# design.net
KiCad netlist of a schematic drawn in Altium Designer
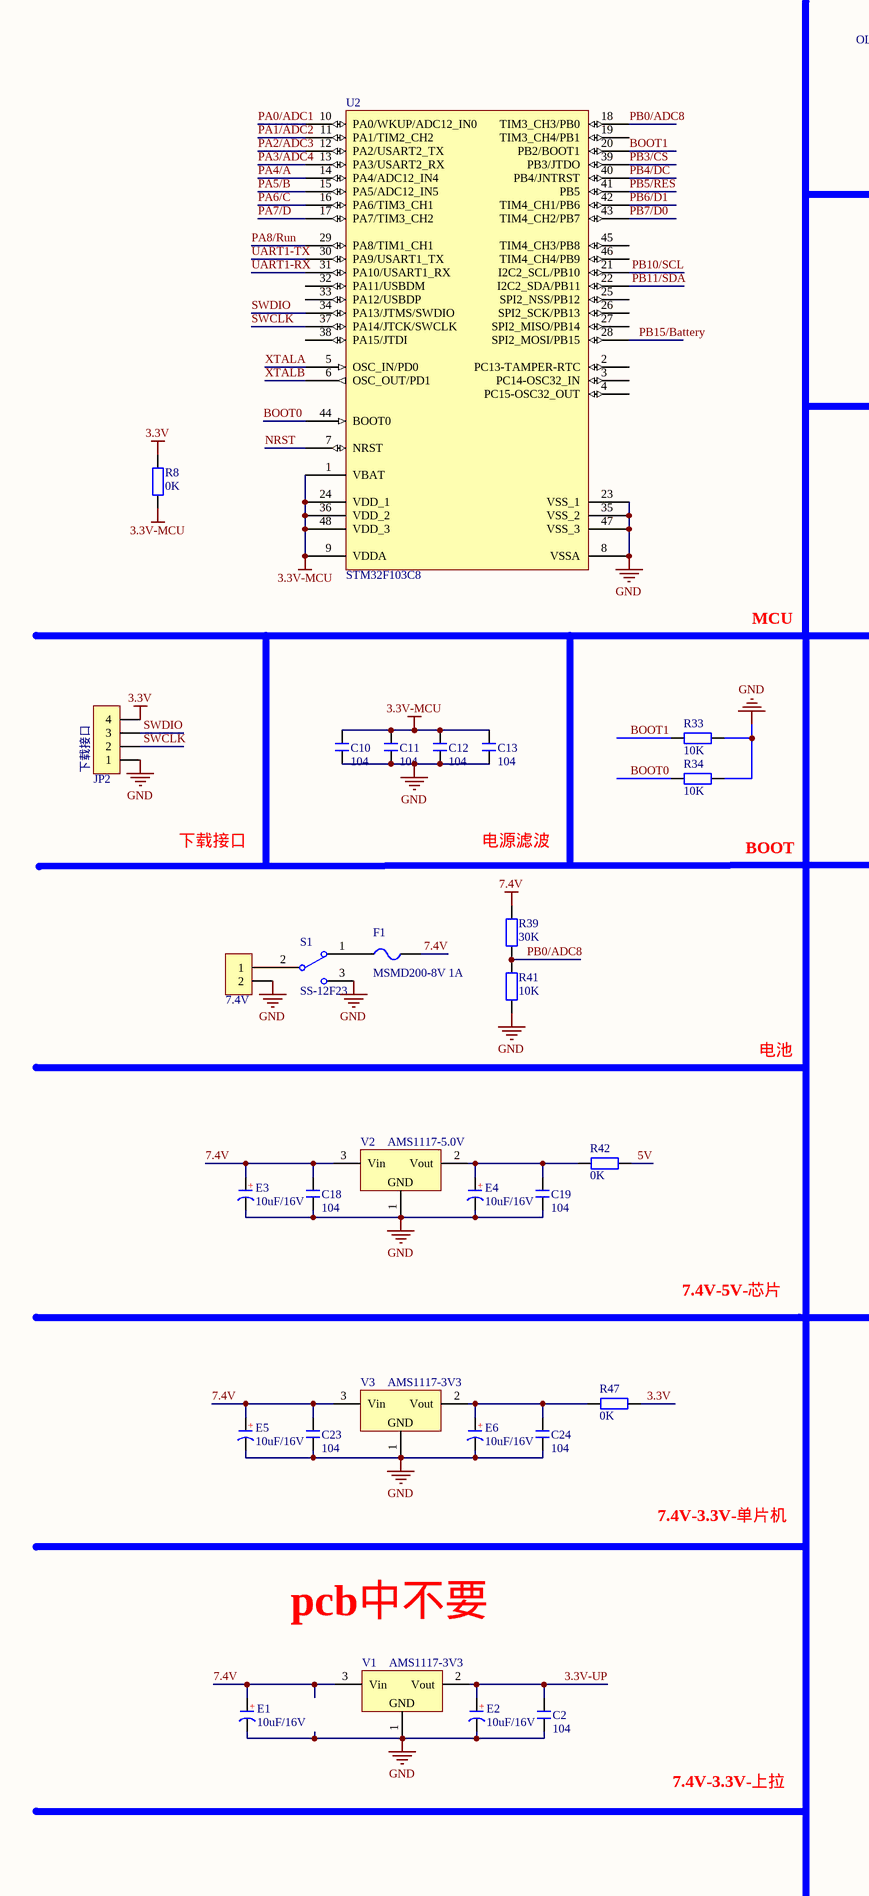
[diagram p0: 足底压力.SchDoc, left]
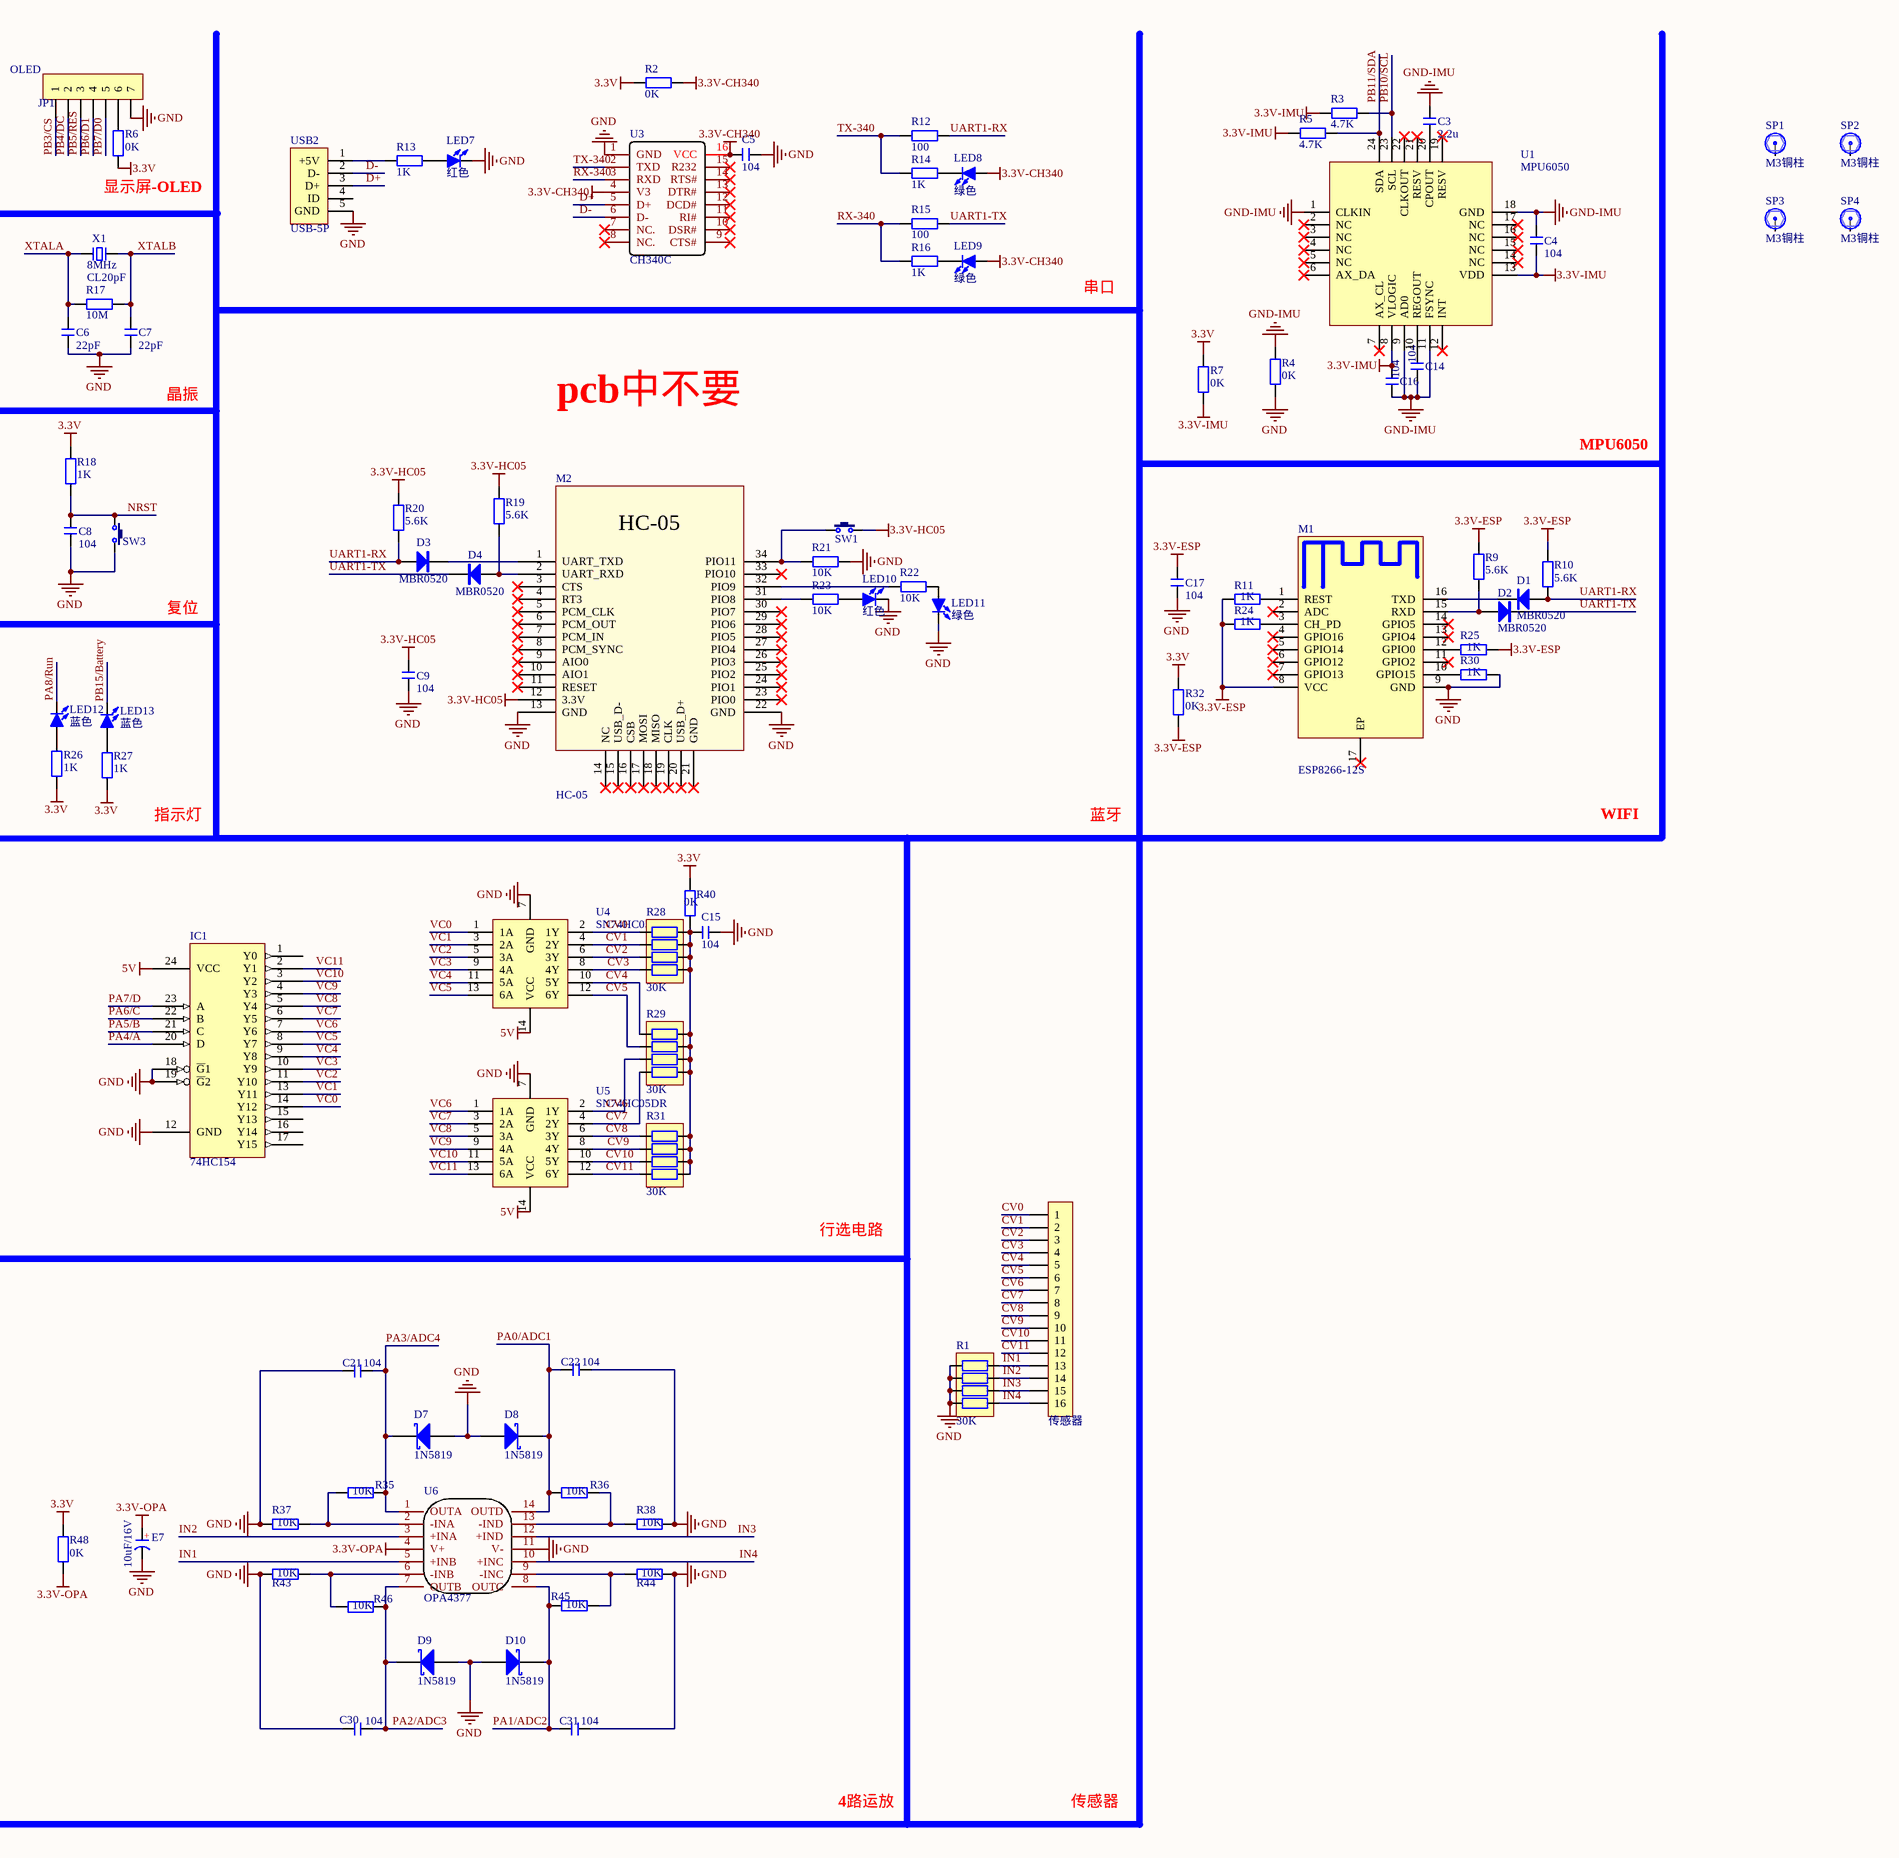
[diagram p1: 足底压力.SchDoc, right]

(export (version "E")
  (design (tool "Eeschema 10.0.6"))
  (components
    (comp (ref "7.4V")
      (value "HDR-1X2")
      (footprint "XH2.54-WI-2P")
      (description "2P接插件")
      (fields (field (name "版权归属") "封装库来自淘宝 ID：黄晶宝石"))
      (libsource (lib "5.3 - 接插件-脚距2.54 (100mil) ") (part "Header 2"))
    )
    (comp (ref "C2")
      (value "104")
      (footprint "C 0603_L")
      (description "贴片电容")
      (libsource (lib "0.1 - 电阻-电容-电感") (part "C"))
    )
    (comp (ref "C3")
      (value "2.2u")
      (footprint "C 0603_L")
      (description "贴片电容")
      (libsource (lib "0.1 - 电阻-电容-电感") (part "C"))
    )
    (comp (ref "C4")
      (value "104")
      (footprint "C 0603_L")
      (description "贴片电容")
      (libsource (lib "0.1 - 电阻-电容-电感") (part "C"))
    )
    (comp (ref "C5")
      (value "104")
      (footprint "C 0603_L")
      (description "贴片电容")
      (libsource (lib "0.1 - 电阻-电容-电感") (part "C"))
    )
    (comp (ref "C6")
      (value "22pF")
      (footprint "C 0603_L")
      (description "贴片电容")
      (libsource (lib "0.1 - 电阻-电容-电感") (part "C"))
    )
    (comp (ref "C7")
      (value "22pF")
      (footprint "C 0603_L")
      (description "贴片电容")
      (libsource (lib "0.1 - 电阻-电容-电感") (part "C"))
    )
    (comp (ref "C8")
      (value "104")
      (footprint "C 0603_L")
      (description "贴片电容")
      (libsource (lib "0.1 - 电阻-电容-电感") (part "C"))
    )
    (comp (ref "C9")
      (value "104")
      (footprint "C 0805_L")
      (description "贴片电容")
      (libsource (lib "0.1 - 电阻-电容-电感") (part "C"))
    )
    (comp (ref "C10")
      (value "104")
      (footprint "C 0603_L")
      (description "贴片电容")
      (libsource (lib "0.1 - 电阻-电容-电感") (part "C"))
    )
    (comp (ref "C11")
      (value "104")
      (footprint "C 0603_L")
      (description "贴片电容")
      (libsource (lib "0.1 - 电阻-电容-电感") (part "C"))
    )
    (comp (ref "C12")
      (value "104")
      (footprint "C 0603_L")
      (description "贴片电容")
      (libsource (lib "0.1 - 电阻-电容-电感") (part "C"))
    )
    (comp (ref "C13")
      (value "104")
      (footprint "C 0603_L")
      (description "贴片电容")
      (libsource (lib "0.1 - 电阻-电容-电感") (part "C"))
    )
    (comp (ref "C14")
      (value "104")
      (footprint "C 0603_L")
      (description "贴片电容")
      (libsource (lib "0.1 - 电阻-电容-电感") (part "C"))
    )
    (comp (ref "C15")
      (value "104")
      (footprint "C 0603_L")
      (description "贴片电容")
      (libsource (lib "0.1 - 电阻-电容-电感") (part "C"))
    )
    (comp (ref "C16")
      (value "104")
      (footprint "C 0603_L")
      (description "贴片电容")
      (libsource (lib "0.1 - 电阻-电容-电感") (part "C"))
    )
    (comp (ref "C17")
      (value "104")
      (footprint "C 0603_L")
      (description "贴片电容")
      (libsource (lib "0.1 - 电阻-电容-电感") (part "C"))
    )
    (comp (ref "C18")
      (value "104")
      (footprint "C 0603_L")
      (description "贴片电容")
      (libsource (lib "0.1 - 电阻-电容-电感") (part "C"))
    )
    (comp (ref "C19")
      (value "104")
      (footprint "C 0603_L")
      (description "贴片电容")
      (libsource (lib "0.1 - 电阻-电容-电感") (part "C"))
    )
    (comp (ref "C21")
      (value "104")
      (footprint "C 0603_L")
      (description "贴片电容")
      (libsource (lib "0.1 - 电阻-电容-电感") (part "C"))
    )
    (comp (ref "C22")
      (value "104")
      (footprint "C 0603_L")
      (description "贴片电容")
      (libsource (lib "0.1 - 电阻-电容-电感") (part "C"))
    )
    (comp (ref "C23")
      (value "104")
      (footprint "C 0603_L")
      (description "贴片电容")
      (libsource (lib "0.1 - 电阻-电容-电感") (part "C"))
    )
    (comp (ref "C24")
      (value "104")
      (footprint "C 0603_L")
      (description "贴片电容")
      (libsource (lib "0.1 - 电阻-电容-电感") (part "C"))
    )
    (comp (ref "C30")
      (value "104")
      (footprint "C 0603_L")
      (description "贴片电容")
      (libsource (lib "0.1 - 电阻-电容-电感") (part "C"))
    )
    (comp (ref "C31")
      (value "104")
      (footprint "C 0603_L")
      (description "贴片电容")
      (libsource (lib "0.1 - 电阻-电容-电感") (part "C"))
    )
    (comp (ref "D1")
      (value "MBR0520")
      (footprint "SOD-123")
      (description "整流二极管")
      (libsource (lib "0.2 -  二极管-整流桥") (part "1N4007"))
    )
    (comp (ref "D2")
      (value "MBR0520")
      (footprint "SOD-123")
      (description "整流二极管")
      (libsource (lib "0.2 -  二极管-整流桥") (part "1N4007"))
    )
    (comp (ref "D3")
      (value "MBR0520")
      (footprint "SOD-123")
      (description "整流二极管")
      (libsource (lib "0.2 -  二极管-整流桥") (part "1N4007"))
    )
    (comp (ref "D4")
      (value "MBR0520")
      (footprint "SOD-123")
      (description "整流二极管")
      (libsource (lib "0.2 -  二极管-整流桥") (part "1N4007"))
    )
    (comp (ref "D7")
      (value "1N5819")
      (footprint "SOD-123")
      (description "肖特基二极管")
      (libsource (lib "0.2 -  二极管-整流桥") (part "1N5819"))
    )
    (comp (ref "D8")
      (value "1N5819")
      (footprint "SOD-123")
      (description "肖特基二极管")
      (libsource (lib "0.2 -  二极管-整流桥") (part "1N5819"))
    )
    (comp (ref "D9")
      (value "1N5819")
      (footprint "SOD-123")
      (description "肖特基二极管")
      (libsource (lib "0.2 -  二极管-整流桥") (part "1N5819"))
    )
    (comp (ref "D10")
      (value "1N5819")
      (footprint "SOD-123")
      (description "肖特基二极管")
      (libsource (lib "0.2 -  二极管-整流桥") (part "1N5819"))
    )
    (comp (ref "E1")
      (value "10uF/16V")
      (footprint "CD A(3216)")
      (description "贴片钽电容")
      (libsource (lib "0.1 - 电阻-电容-电感") (part "CT"))
    )
    (comp (ref "E2")
      (value "10uF/16V")
      (footprint "CD A(3216)")
      (description "贴片钽电容")
      (libsource (lib "0.1 - 电阻-电容-电感") (part "CT"))
    )
    (comp (ref "E3")
      (value "10uF/16V")
      (footprint "CD A(3216)")
      (description "贴片钽电容")
      (libsource (lib "0.1 - 电阻-电容-电感") (part "CT"))
    )
    (comp (ref "E4")
      (value "10uF/16V")
      (footprint "CD A(3216)")
      (description "贴片钽电容")
      (libsource (lib "0.1 - 电阻-电容-电感") (part "CT"))
    )
    (comp (ref "E5")
      (value "10uF/16V")
      (footprint "CD A(3216)")
      (description "贴片钽电容")
      (libsource (lib "0.1 - 电阻-电容-电感") (part "CT"))
    )
    (comp (ref "E6")
      (value "10uF/16V")
      (footprint "CD A(3216)")
      (description "贴片钽电容")
      (libsource (lib "0.1 - 电阻-电容-电感") (part "CT"))
    )
    (comp (ref "E7")
      (value "10uF/16V")
      (footprint "CD A(3216)")
      (description "贴片钽电容")
      (libsource (lib "0.1 - 电阻-电容-电感") (part "CT"))
    )
    (comp (ref "F1")
      (value "MSMD200-8V 1A")
      (footprint "FU 1206")
      (description "贴片保险丝")
      (fields (field (name "版权归属") "封装库来自淘宝卖家 ID：黄晶宝石"))
      (libsource (lib "2.0 - 保险丝-晶振-光耦") (part "FU"))
    )
    (comp (ref "IC1")
      (value "74HC154")
      (footprint "SOP24_N")
      (description "4线转16线译码器")
      (fields (field (name "版权归属") "源创客"))
      (libsource (lib "74系列芯片") (part "74HC154"))
    )
    (comp (ref "JP1")
      (value "HDR-1X7")
      (footprint "HDR2.54-M-LI-7P")
      (description "7P接插件")
      (fields (field (name "版权归属") "封装库来自淘宝 ID：黄晶宝石"))
      (libsource (lib "5.3 - 接插件-脚距2.54 (100mil) ") (part "Header 7"))
    )
    (comp (ref "JP2")
      (value "HDR-1X4")
      (footprint "HDR2.54-LI-4P")
      (description "4P接插件")
      (fields (field (name "版权归属") "封装库来自淘宝 ID：黄晶宝石"))
      (libsource (lib "5.3 - 接插件-脚距2.54 (100mil) ") (part "Header 4"))
    )
    (comp (ref "LED7")
      (value "红色")
      (footprint "LED 0603R")
      (description "贴片LED")
      (fields (field (name "版权归属") "封装库来自淘宝 ID：黄晶宝石"))
      (libsource (lib "0.3 - LED发光二极管") (part "LED-SMD"))
    )
    (comp (ref "LED8")
      (value "绿色")
      (footprint "LED 0603G")
      (description "贴片LED")
      (fields (field (name "版权归属") "封装库来自淘宝 ID：黄晶宝石"))
      (libsource (lib "0.3 - LED发光二极管") (part "LED-SMD"))
    )
    (comp (ref "LED9")
      (value "绿色")
      (footprint "LED 0603G")
      (description "贴片LED")
      (fields (field (name "版权归属") "封装库来自淘宝 ID：黄晶宝石"))
      (libsource (lib "0.3 - LED发光二极管") (part "LED-SMD"))
    )
    (comp (ref "LED10")
      (value "红色")
      (footprint "LED 0805R")
      (description "贴片LED")
      (fields (field (name "版权归属") "封装库来自淘宝 ID：黄晶宝石"))
      (libsource (lib "0.3 - LED发光二极管") (part "LED-SMD"))
    )
    (comp (ref "LED11")
      (value "绿色")
      (footprint "LED 0805G")
      (description "贴片LED")
      (fields (field (name "版权归属") "封装库来自淘宝 ID：黄晶宝石"))
      (libsource (lib "0.3 - LED发光二极管") (part "LED-SMD"))
    )
    (comp (ref "LED12")
      (value "蓝色")
      (footprint "LED 0603B")
      (description "贴片LED")
      (fields (field (name "版权归属") "封装库来自淘宝 ID：黄晶宝石"))
      (libsource (lib "0.3 - LED发光二极管") (part "LED-SMD"))
    )
    (comp (ref "LED13")
      (value "蓝色")
      (footprint "LED 0603B")
      (description "贴片LED")
      (fields (field (name "版权归属") "封装库来自淘宝 ID：黄晶宝石"))
      (libsource (lib "0.3 - LED发光二极管") (part "LED-SMD"))
    )
    (comp (ref "M1")
      (value "ESP8266-12S")
      (footprint "ESP8266-12S")
      (description "立创商城")
      (libsource (lib "模块") (part "ESP8266-12S"))
    )
    (comp (ref "M2")
      (value "HC-05")
      (footprint "HC-05")
      (description "串口蓝牙模块")
      (fields (field (name "版权归属") "源创客"))
      (libsource (lib "模块") (part "HC-05"))
    )
    (comp (ref "R1")
      (value "30K")
      (footprint "RCA-8P4R-0603")
      (description "贴片排阻")
      (fields (field (name "版权归属") "封装库来自淘宝 ID：黄晶宝石"))
      (libsource (lib "") (part "R-8P4R_1"))
    )
    (comp (ref "R2")
      (value "0K")
      (footprint "R 0402_L")
      (description "贴片电阻")
      (fields (field (name "版权归属") "来自淘宝 ID：黄晶宝石"))
      (libsource (lib "0.1 - 电阻-电容-电感") (part "R"))
    )
    (comp (ref "R3")
      (value "4.7K")
      (footprint "R 0603_L")
      (description "贴片电阻")
      (fields (field (name "版权归属") "来自淘宝 ID：黄晶宝石"))
      (libsource (lib "0.1 - 电阻-电容-电感") (part "R"))
    )
    (comp (ref "R4")
      (value "0K")
      (footprint "R 0402_L")
      (description "贴片电阻")
      (fields (field (name "版权归属") "来自淘宝 ID：黄晶宝石"))
      (libsource (lib "0.1 - 电阻-电容-电感") (part "R"))
    )
    (comp (ref "R5")
      (value "4.7K")
      (footprint "R 0603_L")
      (description "贴片电阻")
      (fields (field (name "版权归属") "来自淘宝 ID：黄晶宝石"))
      (libsource (lib "0.1 - 电阻-电容-电感") (part "R"))
    )
    (comp (ref "R6")
      (value "0K")
      (footprint "R 0402_L")
      (description "贴片电阻")
      (fields (field (name "版权归属") "来自淘宝 ID：黄晶宝石"))
      (libsource (lib "0.1 - 电阻-电容-电感") (part "R"))
    )
    (comp (ref "R7")
      (value "0K")
      (footprint "R 0402_L")
      (description "贴片电阻")
      (fields (field (name "版权归属") "来自淘宝 ID：黄晶宝石"))
      (libsource (lib "0.1 - 电阻-电容-电感") (part "R"))
    )
    (comp (ref "R8")
      (value "0K")
      (footprint "R 0402_L")
      (description "贴片电阻")
      (fields (field (name "版权归属") "来自淘宝 ID：黄晶宝石"))
      (libsource (lib "0.1 - 电阻-电容-电感") (part "R"))
    )
    (comp (ref "R9")
      (value "5.6K")
      (footprint "R 0603_L")
      (description "贴片电阻")
      (fields (field (name "版权归属") "来自淘宝 ID：黄晶宝石"))
      (libsource (lib "0.1 - 电阻-电容-电感") (part "R"))
    )
    (comp (ref "R10")
      (value "5.6K")
      (footprint "R 0603_L")
      (description "贴片电阻")
      (fields (field (name "版权归属") "来自淘宝 ID：黄晶宝石"))
      (libsource (lib "0.1 - 电阻-电容-电感") (part "R"))
    )
    (comp (ref "R11")
      (value "1K")
      (footprint "R 0603_L")
      (description "贴片电阻")
      (fields (field (name "版权归属") "来自淘宝 ID：黄晶宝石"))
      (libsource (lib "0.1 - 电阻-电容-电感") (part "R"))
    )
    (comp (ref "R12")
      (value "100")
      (footprint "R 0603_L")
      (description "贴片电阻")
      (fields (field (name "版权归属") "来自淘宝 ID：黄晶宝石"))
      (libsource (lib "0.1 - 电阻-电容-电感") (part "R"))
    )
    (comp (ref "R13")
      (value "1K")
      (footprint "R 0603_L")
      (description "贴片电阻")
      (fields (field (name "版权归属") "来自淘宝 ID：黄晶宝石"))
      (libsource (lib "0.1 - 电阻-电容-电感") (part "R"))
    )
    (comp (ref "R14")
      (value "1K")
      (footprint "R 0603_L")
      (description "贴片电阻")
      (fields (field (name "版权归属") "来自淘宝 ID：黄晶宝石"))
      (libsource (lib "0.1 - 电阻-电容-电感") (part "R"))
    )
    (comp (ref "R15")
      (value "100")
      (footprint "R 0603_L")
      (description "贴片电阻")
      (fields (field (name "版权归属") "来自淘宝 ID：黄晶宝石"))
      (libsource (lib "0.1 - 电阻-电容-电感") (part "R"))
    )
    (comp (ref "R16")
      (value "1K")
      (footprint "R 0603_L")
      (description "贴片电阻")
      (fields (field (name "版权归属") "来自淘宝 ID：黄晶宝石"))
      (libsource (lib "0.1 - 电阻-电容-电感") (part "R"))
    )
    (comp (ref "R17")
      (value "10M")
      (footprint "R 0603_L")
      (description "贴片电阻")
      (fields (field (name "版权归属") "来自淘宝 ID：黄晶宝石"))
      (libsource (lib "0.1 - 电阻-电容-电感") (part "R"))
    )
    (comp (ref "R18")
      (value "1K")
      (footprint "R 0603_L")
      (description "贴片电阻")
      (fields (field (name "版权归属") "来自淘宝 ID：黄晶宝石"))
      (libsource (lib "0.1 - 电阻-电容-电感") (part "R"))
    )
    (comp (ref "R19")
      (value "5.6K")
      (footprint "R 0805_L")
      (description "贴片电阻")
      (fields (field (name "版权归属") "来自淘宝 ID：黄晶宝石"))
      (libsource (lib "0.1 - 电阻-电容-电感") (part "R"))
    )
    (comp (ref "R20")
      (value "5.6K")
      (footprint "R 0805_L")
      (description "贴片电阻")
      (fields (field (name "版权归属") "来自淘宝 ID：黄晶宝石"))
      (libsource (lib "0.1 - 电阻-电容-电感") (part "R"))
    )
    (comp (ref "R21")
      (value "10K")
      (footprint "R 0805_L")
      (description "贴片电阻")
      (fields (field (name "版权归属") "来自淘宝 ID：黄晶宝石"))
      (libsource (lib "0.1 - 电阻-电容-电感") (part "R"))
    )
    (comp (ref "R22")
      (value "10K")
      (footprint "R 0805_L")
      (description "贴片电阻")
      (fields (field (name "版权归属") "来自淘宝 ID：黄晶宝石"))
      (libsource (lib "0.1 - 电阻-电容-电感") (part "R"))
    )
    (comp (ref "R23")
      (value "10K")
      (footprint "R 0805_L")
      (description "贴片电阻")
      (fields (field (name "版权归属") "来自淘宝 ID：黄晶宝石"))
      (libsource (lib "0.1 - 电阻-电容-电感") (part "R"))
    )
    (comp (ref "R24")
      (value "1K")
      (footprint "R 0603_L")
      (description "贴片电阻")
      (fields (field (name "版权归属") "来自淘宝 ID：黄晶宝石"))
      (libsource (lib "0.1 - 电阻-电容-电感") (part "R"))
    )
    (comp (ref "R25")
      (value "1K")
      (footprint "R 0603_L")
      (description "贴片电阻")
      (fields (field (name "版权归属") "来自淘宝 ID：黄晶宝石"))
      (libsource (lib "0.1 - 电阻-电容-电感") (part "R"))
    )
    (comp (ref "R26")
      (value "1K")
      (footprint "R 0603_L")
      (description "贴片电阻")
      (fields (field (name "版权归属") "来自淘宝 ID：黄晶宝石"))
      (libsource (lib "0.1 - 电阻-电容-电感") (part "R"))
    )
    (comp (ref "R27")
      (value "1K")
      (footprint "R 0603_L")
      (description "贴片电阻")
      (fields (field (name "版权归属") "来自淘宝 ID：黄晶宝石"))
      (libsource (lib "0.1 - 电阻-电容-电感") (part "R"))
    )
    (comp (ref "R28")
      (value "30K")
      (footprint "RCA-8P4R-0603")
      (description "贴片排阻")
      (fields (field (name "版权归属") "封装库来自淘宝 ID：黄晶宝石"))
      (libsource (lib "0.1 - 电阻-电容-电感") (part "R-8P4R"))
    )
    (comp (ref "R29")
      (value "30K")
      (footprint "RCA-8P4R-0603")
      (description "贴片排阻")
      (fields (field (name "版权归属") "封装库来自淘宝 ID：黄晶宝石"))
      (libsource (lib "0.1 - 电阻-电容-电感") (part "R-8P4R"))
    )
    (comp (ref "R30")
      (value "1K")
      (footprint "R 0603_L")
      (description "贴片电阻")
      (fields (field (name "版权归属") "来自淘宝 ID：黄晶宝石"))
      (libsource (lib "0.1 - 电阻-电容-电感") (part "R"))
    )
    (comp (ref "R31")
      (value "30K")
      (footprint "RCA-8P4R-0603")
      (description "贴片排阻")
      (fields (field (name "版权归属") "封装库来自淘宝 ID：黄晶宝石"))
      (libsource (lib "0.1 - 电阻-电容-电感") (part "R-8P4R"))
    )
    (comp (ref "R32")
      (value "0K")
      (footprint "R 0402_L")
      (description "贴片电阻")
      (fields (field (name "版权归属") "来自淘宝 ID：黄晶宝石"))
      (libsource (lib "0.1 - 电阻-电容-电感") (part "R"))
    )
    (comp (ref "R33")
      (value "10K")
      (footprint "R 0603_L")
      (description "贴片电阻")
      (fields (field (name "版权归属") "来自淘宝 ID：黄晶宝石"))
      (libsource (lib "0.1 - 电阻-电容-电感") (part "R"))
    )
    (comp (ref "R34")
      (value "10K")
      (footprint "R 0603_L")
      (description "贴片电阻")
      (fields (field (name "版权归属") "来自淘宝 ID：黄晶宝石"))
      (libsource (lib "0.1 - 电阻-电容-电感") (part "R"))
    )
    (comp (ref "R35")
      (value "10K")
      (footprint "R 0603_L")
      (description "贴片电阻")
      (fields (field (name "版权归属") "来自淘宝 ID：黄晶宝石"))
      (libsource (lib "0.1 - 电阻-电容-电感") (part "R"))
    )
    (comp (ref "R36")
      (value "10K")
      (footprint "R 0603_L")
      (description "贴片电阻")
      (fields (field (name "版权归属") "来自淘宝 ID：黄晶宝石"))
      (libsource (lib "0.1 - 电阻-电容-电感") (part "R"))
    )
    (comp (ref "R37")
      (value "10K")
      (footprint "R 0603_L")
      (description "贴片电阻")
      (fields (field (name "版权归属") "来自淘宝 ID：黄晶宝石"))
      (libsource (lib "0.1 - 电阻-电容-电感") (part "R"))
    )
    (comp (ref "R38")
      (value "10K")
      (footprint "R 0603_L")
      (description "贴片电阻")
      (fields (field (name "版权归属") "来自淘宝 ID：黄晶宝石"))
      (libsource (lib "0.1 - 电阻-电容-电感") (part "R"))
    )
    (comp (ref "R39")
      (value "30K")
      (footprint "R 0603_L")
      (description "贴片电阻")
      (fields (field (name "版权归属") "来自淘宝 ID：黄晶宝石"))
      (libsource (lib "0.1 - 电阻-电容-电感") (part "R"))
    )
    (comp (ref "R40")
      (value "0K")
      (footprint "R 0402_L")
      (description "贴片电阻")
      (fields (field (name "版权归属") "来自淘宝 ID：黄晶宝石"))
      (libsource (lib "0.1 - 电阻-电容-电感") (part "R"))
    )
    (comp (ref "R41")
      (value "10K")
      (footprint "R 0603_L")
      (description "贴片电阻")
      (fields (field (name "版权归属") "来自淘宝 ID：黄晶宝石"))
      (libsource (lib "0.1 - 电阻-电容-电感") (part "R"))
    )
    (comp (ref "R42")
      (value "0K")
      (footprint "R 0402_L")
      (description "贴片电阻")
      (fields (field (name "版权归属") "来自淘宝 ID：黄晶宝石"))
      (libsource (lib "0.1 - 电阻-电容-电感") (part "R"))
    )
    (comp (ref "R43")
      (value "10K")
      (footprint "R 0603_L")
      (description "贴片电阻")
      (fields (field (name "版权归属") "来自淘宝 ID：黄晶宝石"))
      (libsource (lib "0.1 - 电阻-电容-电感") (part "R"))
    )
    (comp (ref "R44")
      (value "10K")
      (footprint "R 0603_L")
      (description "贴片电阻")
      (fields (field (name "版权归属") "来自淘宝 ID：黄晶宝石"))
      (libsource (lib "0.1 - 电阻-电容-电感") (part "R"))
    )
    (comp (ref "R45")
      (value "10K")
      (footprint "R 0603_L")
      (description "贴片电阻")
      (fields (field (name "版权归属") "来自淘宝 ID：黄晶宝石"))
      (libsource (lib "0.1 - 电阻-电容-电感") (part "R"))
    )
    (comp (ref "R46")
      (value "10K")
      (footprint "R 0603_L")
      (description "贴片电阻")
      (fields (field (name "版权归属") "来自淘宝 ID：黄晶宝石"))
      (libsource (lib "0.1 - 电阻-电容-电感") (part "R"))
    )
    (comp (ref "R47")
      (value "0K")
      (footprint "R 0402_L")
      (description "贴片电阻")
      (fields (field (name "版权归属") "来自淘宝 ID：黄晶宝石"))
      (libsource (lib "0.1 - 电阻-电容-电感") (part "R"))
    )
    (comp (ref "R48")
      (value "0K")
      (footprint "R 0402_L")
      (description "贴片电阻")
      (fields (field (name "版权归属") "来自淘宝 ID：黄晶宝石"))
      (libsource (lib "0.1 - 电阻-电容-电感") (part "R"))
    )
    (comp (ref "S1")
      (value "SS-12F23")
      (footprint "SK-12D07VG3")
      (description "1路波动开关")
      (fields (field (name "版权归属") "源创客"))
      (libsource (lib "按键-开关") (part "SSW-1P"))
    )
    (comp (ref "SP1")
      (value "M3铜柱")
      (footprint "M3x20_L")
      (description "铜柱")
      (fields (field (name "版权归属") "封装库来自淘宝 ID：黄晶宝石"))
      (libsource (lib "4.1 - 未分类器件") (part "铜柱小焊盘"))
    )
    (comp (ref "SP2")
      (value "M3铜柱")
      (footprint "M3x20_L")
      (description "铜柱")
      (fields (field (name "版权归属") "封装库来自淘宝 ID：黄晶宝石"))
      (libsource (lib "4.1 - 未分类器件") (part "铜柱小焊盘"))
    )
    (comp (ref "SP3")
      (value "M3铜柱")
      (footprint "M3x20_L")
      (description "铜柱")
      (fields (field (name "版权归属") "封装库来自淘宝 ID：黄晶宝石"))
      (libsource (lib "4.1 - 未分类器件") (part "铜柱小焊盘"))
    )
    (comp (ref "SP4")
      (value "M3铜柱")
      (footprint "M3x20_L")
      (description "铜柱")
      (fields (field (name "版权归属") "封装库来自淘宝 ID：黄晶宝石"))
      (libsource (lib "4.1 - 未分类器件") (part "铜柱小焊盘"))
    )
    (comp (ref "SW1")
      (value "3x6x5")
      (footprint "TSW SMD-3*6*2.5")
      (description "3x6轻触开关")
      (fields (field (name "版权归属") "源创客"))
      (libsource (lib "按键-开关") (part "TSW 3x6"))
    )
    (comp (ref "SW3")
      (value "3x6x5")
      (footprint "TSW SMD-3*6*2.5")
      (description "3x6轻触开关")
      (fields (field (name "版权归属") "源创客"))
      (libsource (lib "") (part "TSW 3x6_1"))
    )
    (comp (ref "U1")
      (value "MPU6050")
      (footprint "QFN24 4x4_L")
      (description "数字运动传感器")
      (fields (field (name "版权归属") "源创客"))
      (libsource (lib "传感元件") (part "MPU6050"))
    )
    (comp (ref "U2")
      (value "STM32F103C8")
      (footprint "LQFP48 7X7_L")
      (description "Flaah:64/RAM:20/IO:36")
      (fields (field (name "版权归属") "源创客"))
      (libsource (lib "STM32系列单片机") (part "STM32F103C8"))
    )
    (comp (ref "U3")
      (value "CH340C")
      (footprint "SOP16")
      (description "串口芯片，无需外部晶振")
      (libsource (lib "1.9 - CH340系列编程器芯片") (part "CH340C"))
    )
    (comp (ref "U4")
      (value "SN74HC05DR")
      (footprint "SOP14")
      (libsource (lib "1.4 - 74系列TTL芯片") (part "SN74HC05DR"))
    )
    (comp (ref "U5")
      (value "SN74HC05DR")
      (footprint "SOP14")
      (libsource (lib "1.4 - 74系列TTL芯片") (part "SN74HC05DR"))
    )
    (comp (ref "U6")
      (value "OPA4377")
      (footprint "TSSOP14_L")
      (description "4路运放")
      (libsource (lib "运放-功放") (part "OPA4377"))
    )
    (comp (ref "USB2")
      (value "USB-5P")
      (footprint "USB-MICRO_A")
      (description "微型USB母座")
      (fields (field (name "版权归属") "源创客"))
      (libsource (lib "接口类") (part "USB-5P"))
    )
    (comp (ref "V1")
      (value "AMS1117-3V3")
      (footprint "SOT223_L")
      (description "三端稳压芯片")
      (libsource (lib "1.1 - 电源类芯片") (part "AMS1117"))
    )
    (comp (ref "V2")
      (value "AMS1117-5.0V")
      (footprint "SOT223_L")
      (description "三端稳压芯片")
      (libsource (lib "1.1 - 电源类芯片") (part "AMS1117"))
    )
    (comp (ref "V3")
      (value "AMS1117-3V3")
      (footprint "SOT223_L")
      (description "三端稳压芯片")
      (libsource (lib "1.1 - 电源类芯片") (part "AMS1117"))
    )
    (comp (ref "X1")
      (value "8MHz")
      (footprint "OSC 5032-2P")
      (description "2脚无源脚晶振")
      (fields (field (name "负载电容") "CL20pF") (field (name "版权归属") "源创客"))
      (libsource (lib "保险丝-晶振") (part "XTAL-2P"))
    )
    (comp (ref "传感器")
      (value "HDR-1X16")
      (footprint "XH2.54-WI-16P")
      (description "16P接插件")
      (fields (field (name "版权归属") "封装库来自淘宝卖家 ID：黄晶宝石"))
      (libsource (lib "5.3 - 接插件-脚距2.54 (100mil) ") (part "Header 16"))
    )
  )
  (nets
    (net (code "1") (name "/3.3V-UP") (class "Default")
      (node (ref "C2") (pin "2") (pinfunction "2_2") (pintype "passive"))
      (node (ref "E2") (pin "1") (pinfunction "A_1") (pintype "passive"))
      (node (ref "V1") (pin "2") (pinfunction "Vout_2") (pintype "passive"))
    )
    (net (code "2") (name "/BOOT0") (class "Default")
      (node (ref "R34") (pin "1") (pinfunction "1_1") (pintype "passive"))
      (node (ref "U2") (pin "44") (pinfunction "BOOT0_44") (pintype "input"))
    )
    (net (code "3") (name "/BOOT1") (class "Default")
      (node (ref "R33") (pin "1") (pinfunction "1_1") (pintype "passive"))
      (node (ref "U2") (pin "20") (pinfunction "PB2/BOOT1_20") (pintype "bidirectional"))
    )
    (net (code "4") (name "/CV0") (class "Default")
      (node (ref "R28") (pin "4") (pinfunction "4_4") (pintype "passive"))
      (node (ref "U4") (pin "2") (pinfunction "1Y_2") (pintype "passive"))
      (node (ref "传感器") (pin "1") (pinfunction "1_1") (pintype "passive"))
    )
    (net (code "5") (name "/CV1") (class "Default")
      (node (ref "R28") (pin "3") (pinfunction "3_3") (pintype "passive"))
      (node (ref "U4") (pin "4") (pinfunction "2Y_4") (pintype "passive"))
      (node (ref "传感器") (pin "2") (pinfunction "2_2") (pintype "passive"))
    )
    (net (code "6") (name "/CV2") (class "Default")
      (node (ref "R28") (pin "2") (pinfunction "2_2") (pintype "passive"))
      (node (ref "U4") (pin "6") (pinfunction "3Y_6") (pintype "passive"))
      (node (ref "传感器") (pin "3") (pinfunction "3_3") (pintype "passive"))
    )
    (net (code "7") (name "/CV3") (class "Default")
      (node (ref "R28") (pin "1") (pinfunction "1_1") (pintype "passive"))
      (node (ref "U4") (pin "8") (pinfunction "4Y_8") (pintype "passive"))
      (node (ref "传感器") (pin "4") (pinfunction "4_4") (pintype "passive"))
    )
    (net (code "8") (name "/CV4") (class "Default")
      (node (ref "R29") (pin "4") (pinfunction "4_4") (pintype "passive"))
      (node (ref "U4") (pin "10") (pinfunction "5Y_10") (pintype "passive"))
      (node (ref "传感器") (pin "5") (pinfunction "5_5") (pintype "passive"))
    )
    (net (code "9") (name "/CV5") (class "Default")
      (node (ref "R29") (pin "3") (pinfunction "3_3") (pintype "passive"))
      (node (ref "U4") (pin "12") (pinfunction "6Y_12") (pintype "passive"))
      (node (ref "传感器") (pin "6") (pinfunction "6_6") (pintype "passive"))
    )
    (net (code "10") (name "/CV6") (class "Default")
      (node (ref "R29") (pin "2") (pinfunction "2_2") (pintype "passive"))
      (node (ref "U5") (pin "2") (pinfunction "1Y_2") (pintype "passive"))
      (node (ref "传感器") (pin "7") (pinfunction "7_7") (pintype "passive"))
    )
    (net (code "11") (name "/CV7") (class "Default")
      (node (ref "R29") (pin "1") (pinfunction "1_1") (pintype "passive"))
      (node (ref "U5") (pin "4") (pinfunction "2Y_4") (pintype "passive"))
      (node (ref "传感器") (pin "8") (pinfunction "8_8") (pintype "passive"))
    )
    (net (code "12") (name "/CV8") (class "Default")
      (node (ref "R31") (pin "4") (pinfunction "4_4") (pintype "passive"))
      (node (ref "U5") (pin "6") (pinfunction "3Y_6") (pintype "passive"))
      (node (ref "传感器") (pin "9") (pinfunction "9_9") (pintype "passive"))
    )
    (net (code "13") (name "/CV9") (class "Default")
      (node (ref "R31") (pin "3") (pinfunction "3_3") (pintype "passive"))
      (node (ref "U5") (pin "8") (pinfunction "4Y_8") (pintype "passive"))
      (node (ref "传感器") (pin "10") (pinfunction "10_10") (pintype "passive"))
    )
    (net (code "14") (name "/CV10") (class "Default")
      (node (ref "R31") (pin "2") (pinfunction "2_2") (pintype "passive"))
      (node (ref "U5") (pin "10") (pinfunction "5Y_10") (pintype "passive"))
      (node (ref "传感器") (pin "11") (pinfunction "11_11") (pintype "passive"))
    )
    (net (code "15") (name "/CV11") (class "Default")
      (node (ref "R31") (pin "1") (pinfunction "1_1") (pintype "passive"))
      (node (ref "U5") (pin "12") (pinfunction "6Y_12") (pintype "passive"))
      (node (ref "传感器") (pin "12") (pinfunction "12_12") (pintype "passive"))
    )
    (net (code "16") (name "/D+") (class "Default")
      (node (ref "U3") (pin "5") (pinfunction "D+_5") (pintype "passive"))
      (node (ref "USB2") (pin "3") (pinfunction "D+_3") (pintype "passive"))
    )
    (net (code "17") (name "/D-") (class "Default")
      (node (ref "U3") (pin "6") (pinfunction "D-_6") (pintype "passive"))
      (node (ref "USB2") (pin "2") (pinfunction "D-_2") (pintype "passive"))
    )
    (net (code "18") (name "/IN1") (class "Default")
      (node (ref "R1") (pin "8") (pinfunction "8_8") (pintype "passive"))
      (node (ref "U6") (pin "5") (pinfunction "+INB_5") (pintype "passive"))
      (node (ref "传感器") (pin "13") (pinfunction "13_13") (pintype "passive"))
    )
    (net (code "19") (name "/IN2") (class "Default")
      (node (ref "R1") (pin "7") (pinfunction "7_7") (pintype "passive"))
      (node (ref "U6") (pin "3") (pinfunction "+INA_3") (pintype "passive"))
      (node (ref "传感器") (pin "14") (pinfunction "14_14") (pintype "passive"))
    )
    (net (code "20") (name "/IN3") (class "Default")
      (node (ref "R1") (pin "6") (pinfunction "6_6") (pintype "passive"))
      (node (ref "U6") (pin "12") (pinfunction "+IND_12") (pintype "passive"))
      (node (ref "传感器") (pin "15") (pinfunction "15_15") (pintype "passive"))
    )
    (net (code "21") (name "/IN4") (class "Default")
      (node (ref "R1") (pin "5") (pinfunction "5_5") (pintype "passive"))
      (node (ref "U6") (pin "10") (pinfunction "+INC_10") (pintype "passive"))
      (node (ref "传感器") (pin "16") (pinfunction "16_16") (pintype "passive"))
    )
    (net (code "22") (name "/NRST") (class "Default")
      (node (ref "C8") (pin "2") (pinfunction "2_2") (pintype "passive"))
      (node (ref "R18") (pin "1") (pinfunction "1_1") (pintype "passive"))
      (node (ref "SW3") (pin "1") (pinfunction "1_1") (pintype "passive"))
      (node (ref "U2") (pin "7") (pinfunction "NRST_7") (pintype "bidirectional"))
    )
    (net (code "23") (name "/PA0{slash}ADC1") (class "Default")
      (node (ref "C22") (pin "1") (pinfunction "1_1") (pintype "passive"))
      (node (ref "D8") (pin "2") (pinfunction "K_2") (pintype "passive"))
      (node (ref "R36") (pin "1") (pinfunction "1_1") (pintype "passive"))
      (node (ref "U2") (pin "10") (pinfunction "PA0/WKUP/ADC12_IN0_10") (pintype "bidirectional"))
      (node (ref "U6") (pin "14") (pinfunction "OUTD_14") (pintype "passive"))
    )
    (net (code "24") (name "/PA1{slash}ADC2") (class "Default")
      (node (ref "C31") (pin "1") (pinfunction "1_1") (pintype "passive"))
      (node (ref "D10") (pin "2") (pinfunction "K_2") (pintype "passive"))
      (node (ref "R45") (pin "1") (pinfunction "1_1") (pintype "passive"))
      (node (ref "U2") (pin "11") (pinfunction "PA1/TIM2_CH2_11") (pintype "bidirectional"))
      (node (ref "U6") (pin "8") (pinfunction "OUTC_8") (pintype "passive"))
    )
    (net (code "25") (name "/PA2{slash}ADC3") (class "Default")
      (node (ref "C30") (pin "1") (pinfunction "1_1") (pintype "passive"))
      (node (ref "D9") (pin "2") (pinfunction "K_2") (pintype "passive"))
      (node (ref "R46") (pin "2") (pinfunction "2_2") (pintype "passive"))
      (node (ref "U2") (pin "12") (pinfunction "PA2/USART2_TX_12") (pintype "bidirectional"))
      (node (ref "U6") (pin "7") (pinfunction "OUTB_7") (pintype "passive"))
    )
    (net (code "26") (name "/PA3{slash}ADC4") (class "Default")
      (node (ref "C21") (pin "2") (pinfunction "2_2") (pintype "passive"))
      (node (ref "D7") (pin "2") (pinfunction "K_2") (pintype "passive"))
      (node (ref "R35") (pin "2") (pinfunction "2_2") (pintype "passive"))
      (node (ref "U2") (pin "13") (pinfunction "PA3/USART2_RX_13") (pintype "bidirectional"))
      (node (ref "U6") (pin "1") (pinfunction "OUTA_1") (pintype "passive"))
    )
    (net (code "27") (name "/PA4{slash}A") (class "Default")
      (node (ref "IC1") (pin "20") (pinfunction "D_20") (pintype "input"))
      (node (ref "U2") (pin "14") (pinfunction "PA4/ADC12_IN4_14") (pintype "bidirectional"))
    )
    (net (code "28") (name "/PA5{slash}B") (class "Default")
      (node (ref "IC1") (pin "21") (pinfunction "C_21") (pintype "input"))
      (node (ref "U2") (pin "15") (pinfunction "PA5/ADC12_IN5_15") (pintype "bidirectional"))
    )
    (net (code "29") (name "/PA6{slash}C") (class "Default")
      (node (ref "IC1") (pin "22") (pinfunction "B_22") (pintype "input"))
      (node (ref "U2") (pin "16") (pinfunction "PA6/TIM3_CH1_16") (pintype "bidirectional"))
    )
    (net (code "30") (name "/PA7{slash}D") (class "Default")
      (node (ref "IC1") (pin "23") (pinfunction "A_23") (pintype "input"))
      (node (ref "U2") (pin "17") (pinfunction "PA7/TIM3_CH2_17") (pintype "bidirectional"))
    )
    (net (code "31") (name "/PA8{slash}Run") (class "Default")
      (node (ref "LED12") (pin "2") (pinfunction "K_2") (pintype "passive"))
      (node (ref "U2") (pin "29") (pinfunction "PA8/TIM1_CH1_29") (pintype "bidirectional"))
    )
    (net (code "32") (name "/PB0{slash}ADC8") (class "Default")
      (node (ref "R39") (pin "1") (pinfunction "1_1") (pintype "passive"))
      (node (ref "R41") (pin "2") (pinfunction "2_2") (pintype "passive"))
      (node (ref "U2") (pin "18") (pinfunction "TIM3_CH3/PB0_18") (pintype "bidirectional"))
    )
    (net (code "33") (name "/PB3{slash}CS") (class "Default")
      (node (ref "JP1") (pin "1") (pinfunction "1_1") (pintype "passive"))
      (node (ref "U2") (pin "39") (pinfunction "PB3/JTDO_39") (pintype "bidirectional"))
    )
    (net (code "34") (name "/PB4{slash}DC") (class "Default")
      (node (ref "JP1") (pin "2") (pinfunction "2_2") (pintype "passive"))
      (node (ref "U2") (pin "40") (pinfunction "PB4/JNTRST_40") (pintype "bidirectional"))
    )
    (net (code "35") (name "/PB5{slash}RES") (class "Default")
      (node (ref "JP1") (pin "3") (pinfunction "3_3") (pintype "passive"))
      (node (ref "U2") (pin "41") (pinfunction "PB5_41") (pintype "bidirectional"))
    )
    (net (code "36") (name "/PB6{slash}D1") (class "Default")
      (node (ref "JP1") (pin "4") (pinfunction "4_4") (pintype "passive"))
      (node (ref "U2") (pin "42") (pinfunction "TIM4_CH1/PB6_42") (pintype "bidirectional"))
    )
    (net (code "37") (name "/PB7{slash}D0") (class "Default")
      (node (ref "JP1") (pin "5") (pinfunction "5_5") (pintype "passive"))
      (node (ref "U2") (pin "43") (pinfunction "TIM4_CH2/PB7_43") (pintype "bidirectional"))
    )
    (net (code "38") (name "/PB10{slash}SCL") (class "Default")
      (node (ref "R3") (pin "2") (pinfunction "2_2") (pintype "passive"))
      (node (ref "U1") (pin "23") (pinfunction "SCL_23") (pintype "passive"))
      (node (ref "U2") (pin "21") (pinfunction "I2C2_SCL/PB10_21") (pintype "bidirectional"))
    )
    (net (code "39") (name "/PB11{slash}SDA") (class "Default")
      (node (ref "R5") (pin "2") (pinfunction "2_2") (pintype "passive"))
      (node (ref "U1") (pin "24") (pinfunction "SDA_24") (pintype "passive"))
      (node (ref "U2") (pin "22") (pinfunction "I2C2_SDA/PB11_22") (pintype "bidirectional"))
    )
    (net (code "40") (name "/PB15{slash}Battery") (class "Default")
      (node (ref "LED13") (pin "2") (pinfunction "K_2") (pintype "passive"))
      (node (ref "U2") (pin "28") (pinfunction "SPI2_MOSI/PB15_28") (pintype "bidirectional"))
    )
    (net (code "41") (name "/RX-340") (class "Default")
      (node (ref "R15") (pin "1") (pinfunction "1_1") (pintype "passive"))
      (node (ref "R16") (pin "1") (pinfunction "1_1") (pintype "passive"))
      (node (ref "U3") (pin "3") (pinfunction "RXD_3") (pintype "passive"))
    )
    (net (code "42") (name "/SWCLK") (class "Default")
      (node (ref "JP2") (pin "2") (pinfunction "2_2") (pintype "passive"))
      (node (ref "U2") (pin "37") (pinfunction "PA14/JTCK/SWCLK_37") (pintype "bidirectional"))
    )
    (net (code "43") (name "/SWDIO") (class "Default")
      (node (ref "JP2") (pin "3") (pinfunction "3_3") (pintype "passive"))
      (node (ref "U2") (pin "34") (pinfunction "PA13/JTMS/SWDIO_34") (pintype "bidirectional"))
    )
    (net (code "44") (name "/TX-340") (class "Default")
      (node (ref "R12") (pin "1") (pinfunction "1_1") (pintype "passive"))
      (node (ref "R14") (pin "1") (pinfunction "1_1") (pintype "passive"))
      (node (ref "U3") (pin "2") (pinfunction "TXD_2") (pintype "passive"))
    )
    (net (code "45") (name "/UART1-RX") (class "Default")
      (node (ref "D1") (pin "1") (pinfunction "A_1") (pintype "passive"))
      (node (ref "D3") (pin "1") (pinfunction "A_1") (pintype "passive"))
      (node (ref "R10") (pin "1") (pinfunction "1_1") (pintype "passive"))
      (node (ref "R12") (pin "2") (pinfunction "2_2") (pintype "passive"))
      (node (ref "R20") (pin "1") (pinfunction "1_1") (pintype "passive"))
      (node (ref "U2") (pin "31") (pinfunction "PA10/USART1_RX_31") (pintype "bidirectional"))
    )
    (net (code "46") (name "/UART1-TX") (class "Default")
      (node (ref "D2") (pin "2") (pinfunction "K_2") (pintype "passive"))
      (node (ref "D4") (pin "2") (pinfunction "K_2") (pintype "passive"))
      (node (ref "R15") (pin "2") (pinfunction "2_2") (pintype "passive"))
      (node (ref "U2") (pin "30") (pinfunction "PA9/USART1_TX_30") (pintype "bidirectional"))
    )
    (net (code "47") (name "/VC0") (class "Default")
      (node (ref "IC1") (pin "14") (pinfunction "Y12_14") (pintype "output"))
      (node (ref "U4") (pin "1") (pinfunction "1A_1") (pintype "passive"))
    )
    (net (code "48") (name "/VC1") (class "Default")
      (node (ref "IC1") (pin "13") (pinfunction "Y11_13") (pintype "output"))
      (node (ref "U4") (pin "3") (pinfunction "2A_3") (pintype "passive"))
    )
    (net (code "49") (name "/VC2") (class "Default")
      (node (ref "IC1") (pin "11") (pinfunction "Y10_11") (pintype "output"))
      (node (ref "U4") (pin "5") (pinfunction "3A_5") (pintype "passive"))
    )
    (net (code "50") (name "/VC3") (class "Default")
      (node (ref "IC1") (pin "10") (pinfunction "Y9_10") (pintype "output"))
      (node (ref "U4") (pin "9") (pinfunction "4A_9") (pintype "passive"))
    )
    (net (code "51") (name "/VC4") (class "Default")
      (node (ref "IC1") (pin "9") (pinfunction "Y8_9") (pintype "output"))
      (node (ref "U4") (pin "11") (pinfunction "5A_11") (pintype "passive"))
    )
    (net (code "52") (name "/VC5") (class "Default")
      (node (ref "IC1") (pin "8") (pinfunction "Y7_8") (pintype "output"))
      (node (ref "U4") (pin "13") (pinfunction "6A_13") (pintype "passive"))
    )
    (net (code "53") (name "/VC6") (class "Default")
      (node (ref "IC1") (pin "7") (pinfunction "Y6_7") (pintype "output"))
      (node (ref "U5") (pin "1") (pinfunction "1A_1") (pintype "passive"))
    )
    (net (code "54") (name "/VC7") (class "Default")
      (node (ref "IC1") (pin "6") (pinfunction "Y5_6") (pintype "output"))
      (node (ref "U5") (pin "3") (pinfunction "2A_3") (pintype "passive"))
    )
    (net (code "55") (name "/VC8") (class "Default")
      (node (ref "IC1") (pin "5") (pinfunction "Y4_5") (pintype "output"))
      (node (ref "U5") (pin "5") (pinfunction "3A_5") (pintype "passive"))
    )
    (net (code "56") (name "/VC9") (class "Default")
      (node (ref "IC1") (pin "4") (pinfunction "Y3_4") (pintype "output"))
      (node (ref "U5") (pin "9") (pinfunction "4A_9") (pintype "passive"))
    )
    (net (code "57") (name "/VC10") (class "Default")
      (node (ref "IC1") (pin "3") (pinfunction "Y2_3") (pintype "output"))
      (node (ref "U5") (pin "11") (pinfunction "5A_11") (pintype "passive"))
    )
    (net (code "58") (name "/VC11") (class "Default")
      (node (ref "IC1") (pin "2") (pinfunction "Y1_2") (pintype "output"))
      (node (ref "U5") (pin "13") (pinfunction "6A_13") (pintype "passive"))
    )
    (net (code "59") (name "/XTALA") (class "Default")
      (node (ref "C6") (pin "2") (pinfunction "2_2") (pintype "passive"))
      (node (ref "R17") (pin "1") (pinfunction "1_1") (pintype "passive"))
      (node (ref "U2") (pin "5") (pinfunction "OSC_IN/PD0_5") (pintype "input"))
      (node (ref "X1") (pin "1") (pinfunction "1_1") (pintype "passive"))
    )
    (net (code "60") (name "/XTALB") (class "Default")
      (node (ref "C7") (pin "2") (pinfunction "2_2") (pintype "passive"))
      (node (ref "R17") (pin "2") (pinfunction "2_2") (pintype "passive"))
      (node (ref "U2") (pin "6") (pinfunction "OSC_OUT/PD1_6") (pintype "output"))
      (node (ref "X1") (pin "2") (pinfunction "2_2") (pintype "passive"))
    )
    (net (code "61") (name "3.3V") (class "Default")
      (node (ref "JP2") (pin "4") (pinfunction "4_4") (pintype "passive"))
      (node (ref "R18") (pin "2") (pinfunction "2_2") (pintype "passive"))
      (node (ref "R2") (pin "2") (pinfunction "2_2") (pintype "passive"))
      (node (ref "R26") (pin "2") (pinfunction "2_2") (pintype "passive"))
      (node (ref "R27") (pin "2") (pinfunction "2_2") (pintype "passive"))
      (node (ref "R32") (pin "2") (pinfunction "2_2") (pintype "passive"))
      (node (ref "R40") (pin "2") (pinfunction "2_2") (pintype "passive"))
      (node (ref "R47") (pin "2") (pinfunction "2_2") (pintype "passive"))
      (node (ref "R48") (pin "1") (pinfunction "1_1") (pintype "passive"))
      (node (ref "R6") (pin "1") (pinfunction "1_1") (pintype "passive"))
      (node (ref "R7") (pin "2") (pinfunction "2_2") (pintype "passive"))
      (node (ref "R8") (pin "2") (pinfunction "2_2") (pintype "passive"))
    )
    (net (code "62") (name "3.3V-CH340") (class "Default")
      (node (ref "C5") (pin "1") (pinfunction "1_1") (pintype "passive"))
      (node (ref "LED8") (pin "1") (pinfunction "A_1") (pintype "passive"))
      (node (ref "LED9") (pin "1") (pinfunction "A_1") (pintype "passive"))
      (node (ref "R2") (pin "1") (pinfunction "1_1") (pintype "passive"))
      (node (ref "U3") (pin "16") (pinfunction "VCC_16") (pintype "passive"))
      (node (ref "U3") (pin "4") (pinfunction "V3_4") (pintype "passive"))
    )
    (net (code "63") (name "3.3V-ESP") (class "Default")
      (node (ref "C17") (pin "2") (pinfunction "2_2") (pintype "passive"))
      (node (ref "M1") (pin "8") (pinfunction "VCC_8") (pintype "passive"))
      (node (ref "R10") (pin "2") (pinfunction "2_2") (pintype "passive"))
      (node (ref "R11") (pin "2") (pinfunction "2_2") (pintype "passive"))
      (node (ref "R24") (pin "2") (pinfunction "2_2") (pintype "passive"))
      (node (ref "R25") (pin "1") (pinfunction "1_1") (pintype "passive"))
      (node (ref "R32") (pin "1") (pinfunction "1_1") (pintype "passive"))
      (node (ref "R9") (pin "2") (pinfunction "2_2") (pintype "passive"))
    )
    (net (code "64") (name "3.3V-HC05") (class "Default")
      (node (ref "C9") (pin "2") (pinfunction "2_2") (pintype "passive"))
      (node (ref "M2") (pin "12") (pinfunction "3.3V_12") (pintype "passive"))
      (node (ref "R19") (pin "2") (pinfunction "2_2") (pintype "passive"))
      (node (ref "R20") (pin "2") (pinfunction "2_2") (pintype "passive"))
      (node (ref "SW1") (pin "2") (pinfunction "2_2") (pintype "passive"))
    )
    (net (code "65") (name "3.3V-IMU") (class "Default")
      (node (ref "C16") (pin "2") (pinfunction "2_2") (pintype "passive"))
      (node (ref "C4") (pin "1") (pinfunction "1_1") (pintype "passive"))
      (node (ref "R3") (pin "1") (pinfunction "1_1") (pintype "passive"))
      (node (ref "R5") (pin "1") (pinfunction "1_1") (pintype "passive"))
      (node (ref "R7") (pin "1") (pinfunction "1_1") (pintype "passive"))
      (node (ref "U1") (pin "13") (pinfunction "VDD_13") (pintype "passive"))
      (node (ref "U1") (pin "8") (pinfunction "VLOGIC_8") (pintype "passive"))
    )
    (net (code "66") (name "3.3V-MCU") (class "Default")
      (node (ref "C10") (pin "2") (pinfunction "2_2") (pintype "passive"))
      (node (ref "C11") (pin "2") (pinfunction "2_2") (pintype "passive"))
      (node (ref "C12") (pin "2") (pinfunction "2_2") (pintype "passive"))
      (node (ref "C13") (pin "2") (pinfunction "2_2") (pintype "passive"))
      (node (ref "R8") (pin "1") (pinfunction "1_1") (pintype "passive"))
      (node (ref "U2") (pin "1") (pinfunction "VBAT_1") (pintype "power_in"))
      (node (ref "U2") (pin "24") (pinfunction "VDD_1_24") (pintype "power_in"))
      (node (ref "U2") (pin "36") (pinfunction "VDD_2_36") (pintype "power_in"))
      (node (ref "U2") (pin "48") (pinfunction "VDD_3_48") (pintype "power_in"))
      (node (ref "U2") (pin "9") (pinfunction "VDDA_9") (pintype "power_in"))
    )
    (net (code "67") (name "3.3V-OPA") (class "Default")
      (node (ref "E7") (pin "1") (pinfunction "A_1") (pintype "passive"))
      (node (ref "R48") (pin "2") (pinfunction "2_2") (pintype "passive"))
      (node (ref "U6") (pin "4") (pinfunction "V+_4") (pintype "passive"))
    )
    (net (code "68") (name "5V") (class "Default")
      (node (ref "IC1") (pin "24") (pinfunction "VCC_24") (pintype "power_in"))
      (node (ref "R42") (pin "2") (pinfunction "2_2") (pintype "passive"))
      (node (ref "U4") (pin "14") (pinfunction "VCC_14") (pintype "passive"))
      (node (ref "U5") (pin "14") (pinfunction "VCC_14") (pintype "passive"))
    )
    (net (code "69") (name "7.4V") (class "Default")
      (node (ref "C18") (pin "2") (pinfunction "2_2") (pintype "passive"))
      (node (ref "C23") (pin "2") (pinfunction "2_2") (pintype "passive"))
      (node (ref "E1") (pin "1") (pinfunction "A_1") (pintype "passive"))
      (node (ref "E3") (pin "1") (pinfunction "A_1") (pintype "passive"))
      (node (ref "E5") (pin "1") (pinfunction "A_1") (pintype "passive"))
      (node (ref "F1") (pin "2") (pinfunction "2_2") (pintype "passive"))
      (node (ref "R39") (pin "2") (pinfunction "2_2") (pintype "passive"))
      (node (ref "V1") (pin "3") (pinfunction "Vin_3") (pintype "passive"))
      (node (ref "V2") (pin "3") (pinfunction "Vin_3") (pintype "passive"))
      (node (ref "V3") (pin "3") (pinfunction "Vin_3") (pintype "passive"))
    )
    (net (code "70") (name "GND") (class "Default")
      (node (ref "7.4V") (pin "2") (pinfunction "2_2") (pintype "passive"))
      (node (ref "C10") (pin "1") (pinfunction "1_1") (pintype "passive"))
      (node (ref "C11") (pin "1") (pinfunction "1_1") (pintype "passive"))
      (node (ref "C12") (pin "1") (pinfunction "1_1") (pintype "passive"))
      (node (ref "C13") (pin "1") (pinfunction "1_1") (pintype "passive"))
      (node (ref "C15") (pin "2") (pinfunction "2_2") (pintype "passive"))
      (node (ref "C17") (pin "1") (pinfunction "1_1") (pintype "passive"))
      (node (ref "C18") (pin "1") (pinfunction "1_1") (pintype "passive"))
      (node (ref "C19") (pin "1") (pinfunction "1_1") (pintype "passive"))
      (node (ref "C2") (pin "1") (pinfunction "1_1") (pintype "passive"))
      (node (ref "C21") (pin "1") (pinfunction "1_1") (pintype "passive"))
      (node (ref "C22") (pin "2") (pinfunction "2_2") (pintype "passive"))
      (node (ref "C23") (pin "1") (pinfunction "1_1") (pintype "passive"))
      (node (ref "C24") (pin "1") (pinfunction "1_1") (pintype "passive"))
      (node (ref "C30") (pin "2") (pinfunction "2_2") (pintype "passive"))
      (node (ref "C31") (pin "2") (pinfunction "2_2") (pintype "passive"))
      (node (ref "C5") (pin "2") (pinfunction "2_2") (pintype "passive"))
      (node (ref "C6") (pin "1") (pinfunction "1_1") (pintype "passive"))
      (node (ref "C7") (pin "1") (pinfunction "1_1") (pintype "passive"))
      (node (ref "C8") (pin "1") (pinfunction "1_1") (pintype "passive"))
      (node (ref "C9") (pin "1") (pinfunction "1_1") (pintype "passive"))
      (node (ref "D10") (pin "1") (pinfunction "A_1") (pintype "passive"))
      (node (ref "D7") (pin "1") (pinfunction "A_1") (pintype "passive"))
      (node (ref "D8") (pin "1") (pinfunction "A_1") (pintype "passive"))
      (node (ref "D9") (pin "1") (pinfunction "A_1") (pintype "passive"))
      (node (ref "E1") (pin "2") (pinfunction "K_2") (pintype "passive"))
      (node (ref "E2") (pin "2") (pinfunction "K_2") (pintype "passive"))
      (node (ref "E3") (pin "2") (pinfunction "K_2") (pintype "passive"))
      (node (ref "E4") (pin "2") (pinfunction "K_2") (pintype "passive"))
      (node (ref "E5") (pin "2") (pinfunction "K_2") (pintype "passive"))
      (node (ref "E6") (pin "2") (pinfunction "K_2") (pintype "passive"))
      (node (ref "E7") (pin "2") (pinfunction "K_2") (pintype "passive"))
      (node (ref "IC1") (pin "12") (pinfunction "GND_12") (pintype "power_in"))
      (node (ref "IC1") (pin "18") (pinfunction "~{G}1_18") (pintype "input"))
      (node (ref "IC1") (pin "19") (pinfunction "~{G}2_19") (pintype "input"))
      (node (ref "JP1") (pin "7") (pinfunction "7_7") (pintype "passive"))
      (node (ref "JP2") (pin "1") (pinfunction "1_1") (pintype "passive"))
      (node (ref "LED10") (pin "2") (pinfunction "K_2") (pintype "passive"))
      (node (ref "LED11") (pin "2") (pinfunction "K_2") (pintype "passive"))
      (node (ref "LED7") (pin "2") (pinfunction "K_2") (pintype "passive"))
      (node (ref "M1") (pin "9") (pinfunction "GND_9") (pintype "passive"))
      (node (ref "M2") (pin "13") (pinfunction "GND_13") (pintype "passive"))
      (node (ref "M2") (pin "22") (pinfunction "GND_22") (pintype "passive"))
      (node (ref "R1") (pin "1") (pinfunction "1_1") (pintype "passive"))
      (node (ref "R1") (pin "2") (pinfunction "2_2") (pintype "passive"))
      (node (ref "R1") (pin "3") (pinfunction "3_3") (pintype "passive"))
      (node (ref "R1") (pin "4") (pinfunction "4_4") (pintype "passive"))
      (node (ref "R21") (pin "2") (pinfunction "2_2") (pintype "passive"))
      (node (ref "R30") (pin "1") (pinfunction "1_1") (pintype "passive"))
      (node (ref "R33") (pin "2") (pinfunction "2_2") (pintype "passive"))
      (node (ref "R34") (pin "2") (pinfunction "2_2") (pintype "passive"))
      (node (ref "R37") (pin "2") (pinfunction "2_2") (pintype "passive"))
      (node (ref "R38") (pin "1") (pinfunction "1_1") (pintype "passive"))
      (node (ref "R4") (pin "1") (pinfunction "1_1") (pintype "passive"))
      (node (ref "R41") (pin "1") (pinfunction "1_1") (pintype "passive"))
      (node (ref "R43") (pin "1") (pinfunction "1_1") (pintype "passive"))
      (node (ref "R44") (pin "2") (pinfunction "2_2") (pintype "passive"))
      (node (ref "S1") (pin "3") (pinfunction "3_3") (pintype "passive"))
      (node (ref "SW3") (pin "2") (pinfunction "2_2") (pintype "passive"))
      (node (ref "U2") (pin "23") (pinfunction "VSS_1_23") (pintype "power_in"))
      (node (ref "U2") (pin "35") (pinfunction "VSS_2_35") (pintype "power_in"))
      (node (ref "U2") (pin "47") (pinfunction "VSS_3_47") (pintype "power_in"))
      (node (ref "U2") (pin "8") (pinfunction "VSSA_8") (pintype "power_in"))
      (node (ref "U3") (pin "1") (pinfunction "GND_1") (pintype "passive"))
      (node (ref "U4") (pin "7") (pinfunction "GND_7") (pintype "passive"))
      (node (ref "U5") (pin "7") (pinfunction "GND_7") (pintype "passive"))
      (node (ref "U6") (pin "11") (pinfunction "V-_11") (pintype "passive"))
      (node (ref "USB2") (pin "5") (pinfunction "GND_5") (pintype "passive"))
      (node (ref "V1") (pin "1") (pinfunction "GND_1") (pintype "passive"))
      (node (ref "V2") (pin "1") (pinfunction "GND_1") (pintype "passive"))
      (node (ref "V3") (pin "1") (pinfunction "GND_1") (pintype "passive"))
    )
    (net (code "71") (name "GND-IMU") (class "Default")
      (node (ref "C14") (pin "1") (pinfunction "1_1") (pintype "passive"))
      (node (ref "C16") (pin "1") (pinfunction "1_1") (pintype "passive"))
      (node (ref "C3") (pin "1") (pinfunction "1_1") (pintype "passive"))
      (node (ref "C4") (pin "2") (pinfunction "2_2") (pintype "passive"))
      (node (ref "R4") (pin "2") (pinfunction "2_2") (pintype "passive"))
      (node (ref "U1") (pin "1") (pinfunction "CLKIN_1") (pintype "passive"))
      (node (ref "U1") (pin "11") (pinfunction "FSYNC_11") (pintype "passive"))
      (node (ref "U1") (pin "18") (pinfunction "GND_18") (pintype "passive"))
      (node (ref "U1") (pin "9") (pinfunction "AD0_9") (pintype "passive"))
    )
    (net (code "72") (name "Net-(7.4V-Pad1)") (class "Default")
      (node (ref "7.4V") (pin "1") (pinfunction "1_1") (pintype "passive"))
      (node (ref "S1") (pin "2") (pinfunction "2_2") (pintype "passive"))
    )
    (net (code "73") (name "Net-(C15-Pad1)") (class "Default")
      (node (ref "C15") (pin "1") (pinfunction "1_1") (pintype "passive"))
      (node (ref "R28") (pin "5") (pinfunction "5_5") (pintype "passive"))
      (node (ref "R28") (pin "6") (pinfunction "6_6") (pintype "passive"))
      (node (ref "R28") (pin "7") (pinfunction "7_7") (pintype "passive"))
      (node (ref "R28") (pin "8") (pinfunction "8_8") (pintype "passive"))
      (node (ref "R29") (pin "5") (pinfunction "5_5") (pintype "passive"))
      (node (ref "R29") (pin "6") (pinfunction "6_6") (pintype "passive"))
      (node (ref "R29") (pin "7") (pinfunction "7_7") (pintype "passive"))
      (node (ref "R29") (pin "8") (pinfunction "8_8") (pintype "passive"))
      (node (ref "R31") (pin "5") (pinfunction "5_5") (pintype "passive"))
      (node (ref "R31") (pin "6") (pinfunction "6_6") (pintype "passive"))
      (node (ref "R31") (pin "7") (pinfunction "7_7") (pintype "passive"))
      (node (ref "R31") (pin "8") (pinfunction "8_8") (pintype "passive"))
      (node (ref "R40") (pin "1") (pinfunction "1_1") (pintype "passive"))
    )
    (net (code "74") (name "Net-(D1-K)") (class "Default")
      (node (ref "D1") (pin "2") (pinfunction "K_2") (pintype "passive"))
      (node (ref "M1") (pin "16") (pinfunction "TXD_16") (pintype "passive"))
    )
    (net (code "75") (name "Net-(D2-A)") (class "Default")
      (node (ref "D2") (pin "1") (pinfunction "A_1") (pintype "passive"))
      (node (ref "M1") (pin "15") (pinfunction "RXD_15") (pintype "passive"))
      (node (ref "R9") (pin "1") (pinfunction "1_1") (pintype "passive"))
    )
    (net (code "76") (name "Net-(D3-K)") (class "Default")
      (node (ref "D3") (pin "2") (pinfunction "K_2") (pintype "passive"))
      (node (ref "M2") (pin "1") (pinfunction "UART_TXD_1") (pintype "passive"))
    )
    (net (code "77") (name "Net-(D4-A)") (class "Default")
      (node (ref "D4") (pin "1") (pinfunction "A_1") (pintype "passive"))
      (node (ref "M2") (pin "2") (pinfunction "UART_RXD_2") (pintype "passive"))
      (node (ref "R19") (pin "1") (pinfunction "1_1") (pintype "passive"))
    )
    (net (code "78") (name "Net-(E4-A)") (class "Default")
      (node (ref "C19") (pin "2") (pinfunction "2_2") (pintype "passive"))
      (node (ref "E4") (pin "1") (pinfunction "A_1") (pintype "passive"))
      (node (ref "R42") (pin "1") (pinfunction "1_1") (pintype "passive"))
      (node (ref "V2") (pin "2") (pinfunction "Vout_2") (pintype "passive"))
    )
    (net (code "79") (name "Net-(E6-A)") (class "Default")
      (node (ref "C24") (pin "2") (pinfunction "2_2") (pintype "passive"))
      (node (ref "E6") (pin "1") (pinfunction "A_1") (pintype "passive"))
      (node (ref "R47") (pin "1") (pinfunction "1_1") (pintype "passive"))
      (node (ref "V3") (pin "2") (pinfunction "Vout_2") (pintype "passive"))
    )
    (net (code "80") (name "Net-(F1-Pad1)") (class "Default")
      (node (ref "F1") (pin "1") (pinfunction "1_1") (pintype "passive"))
      (node (ref "S1") (pin "1") (pinfunction "1_1") (pintype "passive"))
    )
    (net (code "81") (name "Net-(JP1-Pad6)") (class "Default")
      (node (ref "JP1") (pin "6") (pinfunction "6_6") (pintype "passive"))
      (node (ref "R6") (pin "2") (pinfunction "2_2") (pintype "passive"))
    )
    (net (code "82") (name "Net-(LED7-A)") (class "Default")
      (node (ref "LED7") (pin "1") (pinfunction "A_1") (pintype "passive"))
      (node (ref "R13") (pin "1") (pinfunction "1_1") (pintype "passive"))
    )
    (net (code "83") (name "Net-(LED8-K)") (class "Default")
      (node (ref "LED8") (pin "2") (pinfunction "K_2") (pintype "passive"))
      (node (ref "R14") (pin "2") (pinfunction "2_2") (pintype "passive"))
    )
    (net (code "84") (name "Net-(LED9-K)") (class "Default")
      (node (ref "LED9") (pin "2") (pinfunction "K_2") (pintype "passive"))
      (node (ref "R16") (pin "2") (pinfunction "2_2") (pintype "passive"))
    )
    (net (code "85") (name "Net-(LED10-A)") (class "Default")
      (node (ref "LED10") (pin "1") (pinfunction "A_1") (pintype "passive"))
      (node (ref "R23") (pin "2") (pinfunction "2_2") (pintype "passive"))
    )
    (net (code "86") (name "Net-(LED11-A)") (class "Default")
      (node (ref "LED11") (pin "1") (pinfunction "A_1") (pintype "passive"))
      (node (ref "R22") (pin "2") (pinfunction "2_2") (pintype "passive"))
    )
    (net (code "87") (name "Net-(LED12-A)") (class "Default")
      (node (ref "LED12") (pin "1") (pinfunction "A_1") (pintype "passive"))
      (node (ref "R26") (pin "1") (pinfunction "1_1") (pintype "passive"))
    )
    (net (code "88") (name "Net-(LED13-A)") (class "Default")
      (node (ref "LED13") (pin "1") (pinfunction "A_1") (pintype "passive"))
      (node (ref "R27") (pin "1") (pinfunction "1_1") (pintype "passive"))
    )
    (net (code "89") (name "Net-(M1-CH_PD)") (class "Default")
      (node (ref "M1") (pin "3") (pinfunction "CH_PD_3") (pintype "passive"))
      (node (ref "R24") (pin "1") (pinfunction "1_1") (pintype "passive"))
    )
    (net (code "90") (name "Net-(M1-GPIO0)") (class "Default")
      (node (ref "M1") (pin "12") (pinfunction "GPIO0_12") (pintype "passive"))
      (node (ref "R25") (pin "2") (pinfunction "2_2") (pintype "passive"))
    )
    (net (code "91") (name "Net-(M1-GPIO15)") (class "Default")
      (node (ref "M1") (pin "10") (pinfunction "GPIO15_10") (pintype "passive"))
      (node (ref "R30") (pin "2") (pinfunction "2_2") (pintype "passive"))
    )
    (net (code "92") (name "Net-(M1-REST)") (class "Default")
      (node (ref "M1") (pin "1") (pinfunction "REST_1") (pintype "passive"))
      (node (ref "R11") (pin "1") (pinfunction "1_1") (pintype "passive"))
    )
    (net (code "93") (name "Net-(M2-PIO8)") (class "Default")
      (node (ref "M2") (pin "31") (pinfunction "PIO8_31") (pintype "passive"))
      (node (ref "R23") (pin "1") (pinfunction "1_1") (pintype "passive"))
    )
    (net (code "94") (name "Net-(M2-PIO9)") (class "Default")
      (node (ref "M2") (pin "32") (pinfunction "PIO9_32") (pintype "passive"))
      (node (ref "R22") (pin "1") (pinfunction "1_1") (pintype "passive"))
    )
    (net (code "95") (name "Net-(M2-PIO11)") (class "Default")
      (node (ref "M2") (pin "34") (pinfunction "PIO11_34") (pintype "passive"))
      (node (ref "R21") (pin "1") (pinfunction "1_1") (pintype "passive"))
      (node (ref "SW1") (pin "1") (pinfunction "1_1") (pintype "passive"))
    )
    (net (code "96") (name "Net-(U1-CPOUT)") (class "Default")
      (node (ref "C3") (pin "2") (pinfunction "2_2") (pintype "passive"))
      (node (ref "U1") (pin "20") (pinfunction "CPOUT_20") (pintype "passive"))
    )
    (net (code "97") (name "Net-(U1-REGOUT)") (class "Default")
      (node (ref "C14") (pin "2") (pinfunction "2_2") (pintype "passive"))
      (node (ref "U1") (pin "10") (pinfunction "REGOUT_10") (pintype "passive"))
    )
    (net (code "98") (name "Net-(U6--INA)") (class "Default")
      (node (ref "R35") (pin "1") (pinfunction "1_1") (pintype "passive"))
      (node (ref "R37") (pin "1") (pinfunction "1_1") (pintype "passive"))
      (node (ref "U6") (pin "2") (pinfunction "-INA_2") (pintype "passive"))
    )
    (net (code "99") (name "Net-(U6--INB)") (class "Default")
      (node (ref "R43") (pin "2") (pinfunction "2_2") (pintype "passive"))
      (node (ref "R46") (pin "1") (pinfunction "1_1") (pintype "passive"))
      (node (ref "U6") (pin "6") (pinfunction "-INB_6") (pintype "passive"))
    )
    (net (code "100") (name "Net-(U6--INC)") (class "Default")
      (node (ref "R44") (pin "1") (pinfunction "1_1") (pintype "passive"))
      (node (ref "R45") (pin "2") (pinfunction "2_2") (pintype "passive"))
      (node (ref "U6") (pin "9") (pinfunction "-INC_9") (pintype "passive"))
    )
    (net (code "101") (name "Net-(U6--IND)") (class "Default")
      (node (ref "R36") (pin "2") (pinfunction "2_2") (pintype "passive"))
      (node (ref "R38") (pin "2") (pinfunction "2_2") (pintype "passive"))
      (node (ref "U6") (pin "13") (pinfunction "-IND_13") (pintype "passive"))
    )
    (net (code "102") (name "Net-(USB2-+5V)") (class "Default")
      (node (ref "R13") (pin "2") (pinfunction "2_2") (pintype "passive"))
      (node (ref "USB2") (pin "1") (pinfunction "+5V_1") (pintype "passive"))
    )
    (net (code "103") (name "unconnected-(IC1-Y0-Pad1)") (class "Default")
      (node (ref "IC1") (pin "1") (pinfunction "Y0_1") (pintype "output"))
    )
    (net (code "104") (name "unconnected-(IC1-Y13-Pad15)") (class "Default")
      (node (ref "IC1") (pin "15") (pinfunction "Y13_15") (pintype "output"))
    )
    (net (code "105") (name "unconnected-(IC1-Y14-Pad16)") (class "Default")
      (node (ref "IC1") (pin "16") (pinfunction "Y14_16") (pintype "output"))
    )
    (net (code "106") (name "unconnected-(IC1-Y15-Pad17)") (class "Default")
      (node (ref "IC1") (pin "17") (pinfunction "Y15_17") (pintype "output"))
    )
    (net (code "107") (name "unconnected-(M1-ADC-Pad2)") (class "Default")
      (node (ref "M1") (pin "2") (pinfunction "ADC_2") (pintype "passive+no_connect"))
    )
    (net (code "108") (name "unconnected-(M1-EP-Pad17)") (class "Default")
      (node (ref "M1") (pin "17") (pinfunction "EP_17") (pintype "passive+no_connect"))
    )
    (net (code "109") (name "unconnected-(M1-GPIO2-Pad11)") (class "Default")
      (node (ref "M1") (pin "11") (pinfunction "GPIO2_11") (pintype "passive+no_connect"))
    )
    (net (code "110") (name "unconnected-(M1-GPIO4-Pad13)") (class "Default")
      (node (ref "M1") (pin "13") (pinfunction "GPIO4_13") (pintype "passive+no_connect"))
    )
    (net (code "111") (name "unconnected-(M1-GPIO5-Pad14)") (class "Default")
      (node (ref "M1") (pin "14") (pinfunction "GPIO5_14") (pintype "passive+no_connect"))
    )
    (net (code "112") (name "unconnected-(M1-GPIO12-Pad6)") (class "Default")
      (node (ref "M1") (pin "6") (pinfunction "GPIO12_6") (pintype "passive+no_connect"))
    )
    (net (code "113") (name "unconnected-(M1-GPIO13-Pad7)") (class "Default")
      (node (ref "M1") (pin "7") (pinfunction "GPIO13_7") (pintype "passive+no_connect"))
    )
    (net (code "114") (name "unconnected-(M1-GPIO14-Pad5)") (class "Default")
      (node (ref "M1") (pin "5") (pinfunction "GPIO14_5") (pintype "passive+no_connect"))
    )
    (net (code "115") (name "unconnected-(M1-GPIO16-Pad4)") (class "Default")
      (node (ref "M1") (pin "4") (pinfunction "GPIO16_4") (pintype "passive+no_connect"))
    )
    (net (code "116") (name "unconnected-(M2-AIO0-Pad9)") (class "Default")
      (node (ref "M2") (pin "9") (pinfunction "AIO0_9") (pintype "passive+no_connect"))
    )
    (net (code "117") (name "unconnected-(M2-AIO1-Pad10)") (class "Default")
      (node (ref "M2") (pin "10") (pinfunction "AIO1_10") (pintype "passive+no_connect"))
    )
    (net (code "118") (name "unconnected-(M2-CLK-Pad19)") (class "Default")
      (node (ref "M2") (pin "19") (pinfunction "CLK_19") (pintype "passive+no_connect"))
    )
    (net (code "119") (name "unconnected-(M2-CSB-Pad16)") (class "Default")
      (node (ref "M2") (pin "16") (pinfunction "CSB_16") (pintype "passive+no_connect"))
    )
    (net (code "120") (name "unconnected-(M2-CTS-Pad3)") (class "Default")
      (node (ref "M2") (pin "3") (pinfunction "CTS_3") (pintype "passive+no_connect"))
    )
    (net (code "121") (name "unconnected-(M2-GND-Pad21)") (class "Default")
      (node (ref "M2") (pin "21") (pinfunction "GND_21") (pintype "passive+no_connect"))
    )
    (net (code "122") (name "unconnected-(M2-MISO-Pad18)") (class "Default")
      (node (ref "M2") (pin "18") (pinfunction "MISO_18") (pintype "passive+no_connect"))
    )
    (net (code "123") (name "unconnected-(M2-MOSI-Pad17)") (class "Default")
      (node (ref "M2") (pin "17") (pinfunction "MOSI_17") (pintype "passive+no_connect"))
    )
    (net (code "124") (name "unconnected-(M2-NC-Pad14)") (class "Default")
      (node (ref "M2") (pin "14") (pinfunction "NC_14") (pintype "passive+no_connect"))
    )
    (net (code "125") (name "unconnected-(M2-PCM_CLK-Pad5)") (class "Default")
      (node (ref "M2") (pin "5") (pinfunction "PCM_CLK_5") (pintype "passive+no_connect"))
    )
    (net (code "126") (name "unconnected-(M2-PCM_IN-Pad7)") (class "Default")
      (node (ref "M2") (pin "7") (pinfunction "PCM_IN_7") (pintype "passive+no_connect"))
    )
    (net (code "127") (name "unconnected-(M2-PCM_OUT-Pad6)") (class "Default")
      (node (ref "M2") (pin "6") (pinfunction "PCM_OUT_6") (pintype "passive+no_connect"))
    )
    (net (code "128") (name "unconnected-(M2-PCM_SYNC-Pad8)") (class "Default")
      (node (ref "M2") (pin "8") (pinfunction "PCM_SYNC_8") (pintype "passive+no_connect"))
    )
    (net (code "129") (name "unconnected-(M2-PIO0-Pad23)") (class "Default")
      (node (ref "M2") (pin "23") (pinfunction "PIO0_23") (pintype "passive+no_connect"))
    )
    (net (code "130") (name "unconnected-(M2-PIO1-Pad24)") (class "Default")
      (node (ref "M2") (pin "24") (pinfunction "PIO1_24") (pintype "passive+no_connect"))
    )
    (net (code "131") (name "unconnected-(M2-PIO2-Pad25)") (class "Default")
      (node (ref "M2") (pin "25") (pinfunction "PIO2_25") (pintype "passive+no_connect"))
    )
    (net (code "132") (name "unconnected-(M2-PIO3-Pad26)") (class "Default")
      (node (ref "M2") (pin "26") (pinfunction "PIO3_26") (pintype "passive+no_connect"))
    )
    (net (code "133") (name "unconnected-(M2-PIO4-Pad27)") (class "Default")
      (node (ref "M2") (pin "27") (pinfunction "PIO4_27") (pintype "passive+no_connect"))
    )
    (net (code "134") (name "unconnected-(M2-PIO5-Pad28)") (class "Default")
      (node (ref "M2") (pin "28") (pinfunction "PIO5_28") (pintype "passive+no_connect"))
    )
    (net (code "135") (name "unconnected-(M2-PIO6-Pad29)") (class "Default")
      (node (ref "M2") (pin "29") (pinfunction "PIO6_29") (pintype "passive+no_connect"))
    )
    (net (code "136") (name "unconnected-(M2-PIO7-Pad30)") (class "Default")
      (node (ref "M2") (pin "30") (pinfunction "PIO7_30") (pintype "passive+no_connect"))
    )
    (net (code "137") (name "unconnected-(M2-PIO10-Pad33)") (class "Default")
      (node (ref "M2") (pin "33") (pinfunction "PIO10_33") (pintype "passive+no_connect"))
    )
    (net (code "138") (name "unconnected-(M2-RESET-Pad11)") (class "Default")
      (node (ref "M2") (pin "11") (pinfunction "RESET_11") (pintype "passive+no_connect"))
    )
    (net (code "139") (name "unconnected-(M2-RT3-Pad4)") (class "Default")
      (node (ref "M2") (pin "4") (pinfunction "RT3_4") (pintype "passive+no_connect"))
    )
    (net (code "140") (name "unconnected-(M2-USB_D+-Pad20)") (class "Default")
      (node (ref "M2") (pin "20") (pinfunction "USB_D+_20") (pintype "passive+no_connect"))
    )
    (net (code "141") (name "unconnected-(M2-USB_D--Pad15)") (class "Default")
      (node (ref "M2") (pin "15") (pinfunction "USB_D-_15") (pintype "passive+no_connect"))
    )
    (net (code "142") (name "unconnected-(SP1-Pad1)") (class "Default")
      (node (ref "SP1") (pin "1") (pinfunction "1_1") (pintype "passive"))
    )
    (net (code "143") (name "unconnected-(SP2-Pad1)") (class "Default")
      (node (ref "SP2") (pin "1") (pinfunction "1_1") (pintype "passive"))
    )
    (net (code "144") (name "unconnected-(SP3-Pad1)") (class "Default")
      (node (ref "SP3") (pin "1") (pinfunction "1_1") (pintype "passive"))
    )
    (net (code "145") (name "unconnected-(SP4-Pad1)") (class "Default")
      (node (ref "SP4") (pin "1") (pinfunction "1_1") (pintype "passive"))
    )
    (net (code "146") (name "unconnected-(U1-AX_CL-Pad7)") (class "Default")
      (node (ref "U1") (pin "7") (pinfunction "AX_CL_7") (pintype "passive+no_connect"))
    )
    (net (code "147") (name "unconnected-(U1-AX_DA-Pad6)") (class "Default")
      (node (ref "U1") (pin "6") (pinfunction "AX_DA_6") (pintype "passive+no_connect"))
    )
    (net (code "148") (name "unconnected-(U1-CLKOUT-Pad22)") (class "Default")
      (node (ref "U1") (pin "22") (pinfunction "CLKOUT_22") (pintype "passive+no_connect"))
    )
    (net (code "149") (name "unconnected-(U1-INT-Pad12)") (class "Default")
      (node (ref "U1") (pin "12") (pinfunction "INT_12") (pintype "passive+no_connect"))
    )
    (net (code "150") (name "unconnected-(U1-NC-Pad2)") (class "Default")
      (node (ref "U1") (pin "2") (pinfunction "NC_2") (pintype "passive+no_connect"))
    )
    (net (code "151") (name "unconnected-(U1-NC-Pad3)") (class "Default")
      (node (ref "U1") (pin "3") (pinfunction "NC_3") (pintype "passive+no_connect"))
    )
    (net (code "152") (name "unconnected-(U1-NC-Pad4)") (class "Default")
      (node (ref "U1") (pin "4") (pinfunction "NC_4") (pintype "passive+no_connect"))
    )
    (net (code "153") (name "unconnected-(U1-NC-Pad5)") (class "Default")
      (node (ref "U1") (pin "5") (pinfunction "NC_5") (pintype "passive+no_connect"))
    )
    (net (code "154") (name "unconnected-(U1-NC-Pad14)") (class "Default")
      (node (ref "U1") (pin "14") (pinfunction "NC_14") (pintype "passive+no_connect"))
    )
    (net (code "155") (name "unconnected-(U1-NC-Pad15)") (class "Default")
      (node (ref "U1") (pin "15") (pinfunction "NC_15") (pintype "passive+no_connect"))
    )
    (net (code "156") (name "unconnected-(U1-NC-Pad16)") (class "Default")
      (node (ref "U1") (pin "16") (pinfunction "NC_16") (pintype "passive+no_connect"))
    )
    (net (code "157") (name "unconnected-(U1-NC-Pad17)") (class "Default")
      (node (ref "U1") (pin "17") (pinfunction "NC_17") (pintype "passive+no_connect"))
    )
    (net (code "158") (name "unconnected-(U1-RESV-Pad19)") (class "Default")
      (node (ref "U1") (pin "19") (pinfunction "RESV_19") (pintype "passive+no_connect"))
    )
    (net (code "159") (name "unconnected-(U1-RESV-Pad21)") (class "Default")
      (node (ref "U1") (pin "21") (pinfunction "RESV_21") (pintype "passive+no_connect"))
    )
    (net (code "160") (name "unconnected-(U2-PA11{slash}USBDM-Pad32)") (class "Default")
      (node (ref "U2") (pin "32") (pinfunction "PA11/USBDM_32") (pintype "bidirectional"))
    )
    (net (code "161") (name "unconnected-(U2-PA12{slash}USBDP-Pad33)") (class "Default")
      (node (ref "U2") (pin "33") (pinfunction "PA12/USBDP_33") (pintype "bidirectional"))
    )
    (net (code "162") (name "unconnected-(U2-PA15{slash}JTDI-Pad38)") (class "Default")
      (node (ref "U2") (pin "38") (pinfunction "PA15/JTDI_38") (pintype "bidirectional"))
    )
    (net (code "163") (name "unconnected-(U2-PC13-TAMPER-RTC-Pad2)") (class "Default")
      (node (ref "U2") (pin "2") (pinfunction "PC13-TAMPER-RTC_2") (pintype "bidirectional"))
    )
    (net (code "164") (name "unconnected-(U2-PC14-OSC32_IN-Pad3)") (class "Default")
      (node (ref "U2") (pin "3") (pinfunction "PC14-OSC32_IN_3") (pintype "bidirectional"))
    )
    (net (code "165") (name "unconnected-(U2-PC15-OSC32_OUT-Pad4)") (class "Default")
      (node (ref "U2") (pin "4") (pinfunction "PC15-OSC32_OUT_4") (pintype "bidirectional"))
    )
    (net (code "166") (name "unconnected-(U2-SPI2_MISO{slash}PB14-Pad27)") (class "Default")
      (node (ref "U2") (pin "27") (pinfunction "SPI2_MISO/PB14_27") (pintype "bidirectional"))
    )
    (net (code "167") (name "unconnected-(U2-SPI2_NSS{slash}PB12-Pad25)") (class "Default")
      (node (ref "U2") (pin "25") (pinfunction "SPI2_NSS/PB12_25") (pintype "bidirectional"))
    )
    (net (code "168") (name "unconnected-(U2-SPI2_SCK{slash}PB13-Pad26)") (class "Default")
      (node (ref "U2") (pin "26") (pinfunction "SPI2_SCK/PB13_26") (pintype "bidirectional"))
    )
    (net (code "169") (name "unconnected-(U2-TIM3_CH4{slash}PB1-Pad19)") (class "Default")
      (node (ref "U2") (pin "19") (pinfunction "TIM3_CH4/PB1_19") (pintype "bidirectional"))
    )
    (net (code "170") (name "unconnected-(U2-TIM4_CH3{slash}PB8-Pad45)") (class "Default")
      (node (ref "U2") (pin "45") (pinfunction "TIM4_CH3/PB8_45") (pintype "bidirectional"))
    )
    (net (code "171") (name "unconnected-(U2-TIM4_CH4{slash}PB9-Pad46)") (class "Default")
      (node (ref "U2") (pin "46") (pinfunction "TIM4_CH4/PB9_46") (pintype "bidirectional"))
    )
    (net (code "172") (name "unconnected-(U3-CTS#-Pad9)") (class "Default")
      (node (ref "U3") (pin "9") (pinfunction "CTS#_9") (pintype "passive+no_connect"))
    )
    (net (code "173") (name "unconnected-(U3-DCD#-Pad12)") (class "Default")
      (node (ref "U3") (pin "12") (pinfunction "DCD#_12") (pintype "passive+no_connect"))
    )
    (net (code "174") (name "unconnected-(U3-DSR#-Pad10)") (class "Default")
      (node (ref "U3") (pin "10") (pinfunction "DSR#_10") (pintype "passive+no_connect"))
    )
    (net (code "175") (name "unconnected-(U3-DTR#-Pad13)") (class "Default")
      (node (ref "U3") (pin "13") (pinfunction "DTR#_13") (pintype "passive+no_connect"))
    )
    (net (code "176") (name "unconnected-(U3-NC.-Pad7)") (class "Default")
      (node (ref "U3") (pin "7") (pinfunction "NC._7") (pintype "passive+no_connect"))
    )
    (net (code "177") (name "unconnected-(U3-NC.-Pad8)") (class "Default")
      (node (ref "U3") (pin "8") (pinfunction "NC._8") (pintype "passive+no_connect"))
    )
    (net (code "178") (name "unconnected-(U3-R232-Pad15)") (class "Default")
      (node (ref "U3") (pin "15") (pinfunction "R232_15") (pintype "passive+no_connect"))
    )
    (net (code "179") (name "unconnected-(U3-RI#-Pad11)") (class "Default")
      (node (ref "U3") (pin "11") (pinfunction "RI#_11") (pintype "passive+no_connect"))
    )
    (net (code "180") (name "unconnected-(U3-RTS#-Pad14)") (class "Default")
      (node (ref "U3") (pin "14") (pinfunction "RTS#_14") (pintype "passive+no_connect"))
    )
    (net (code "181") (name "unconnected-(USB2-ID-Pad4)") (class "Default")
      (node (ref "USB2") (pin "4") (pinfunction "ID_4") (pintype "passive"))
    )
  )
)
